# io-board-b-h.net
KiCad netlist of a schematic drawn in EAGLE
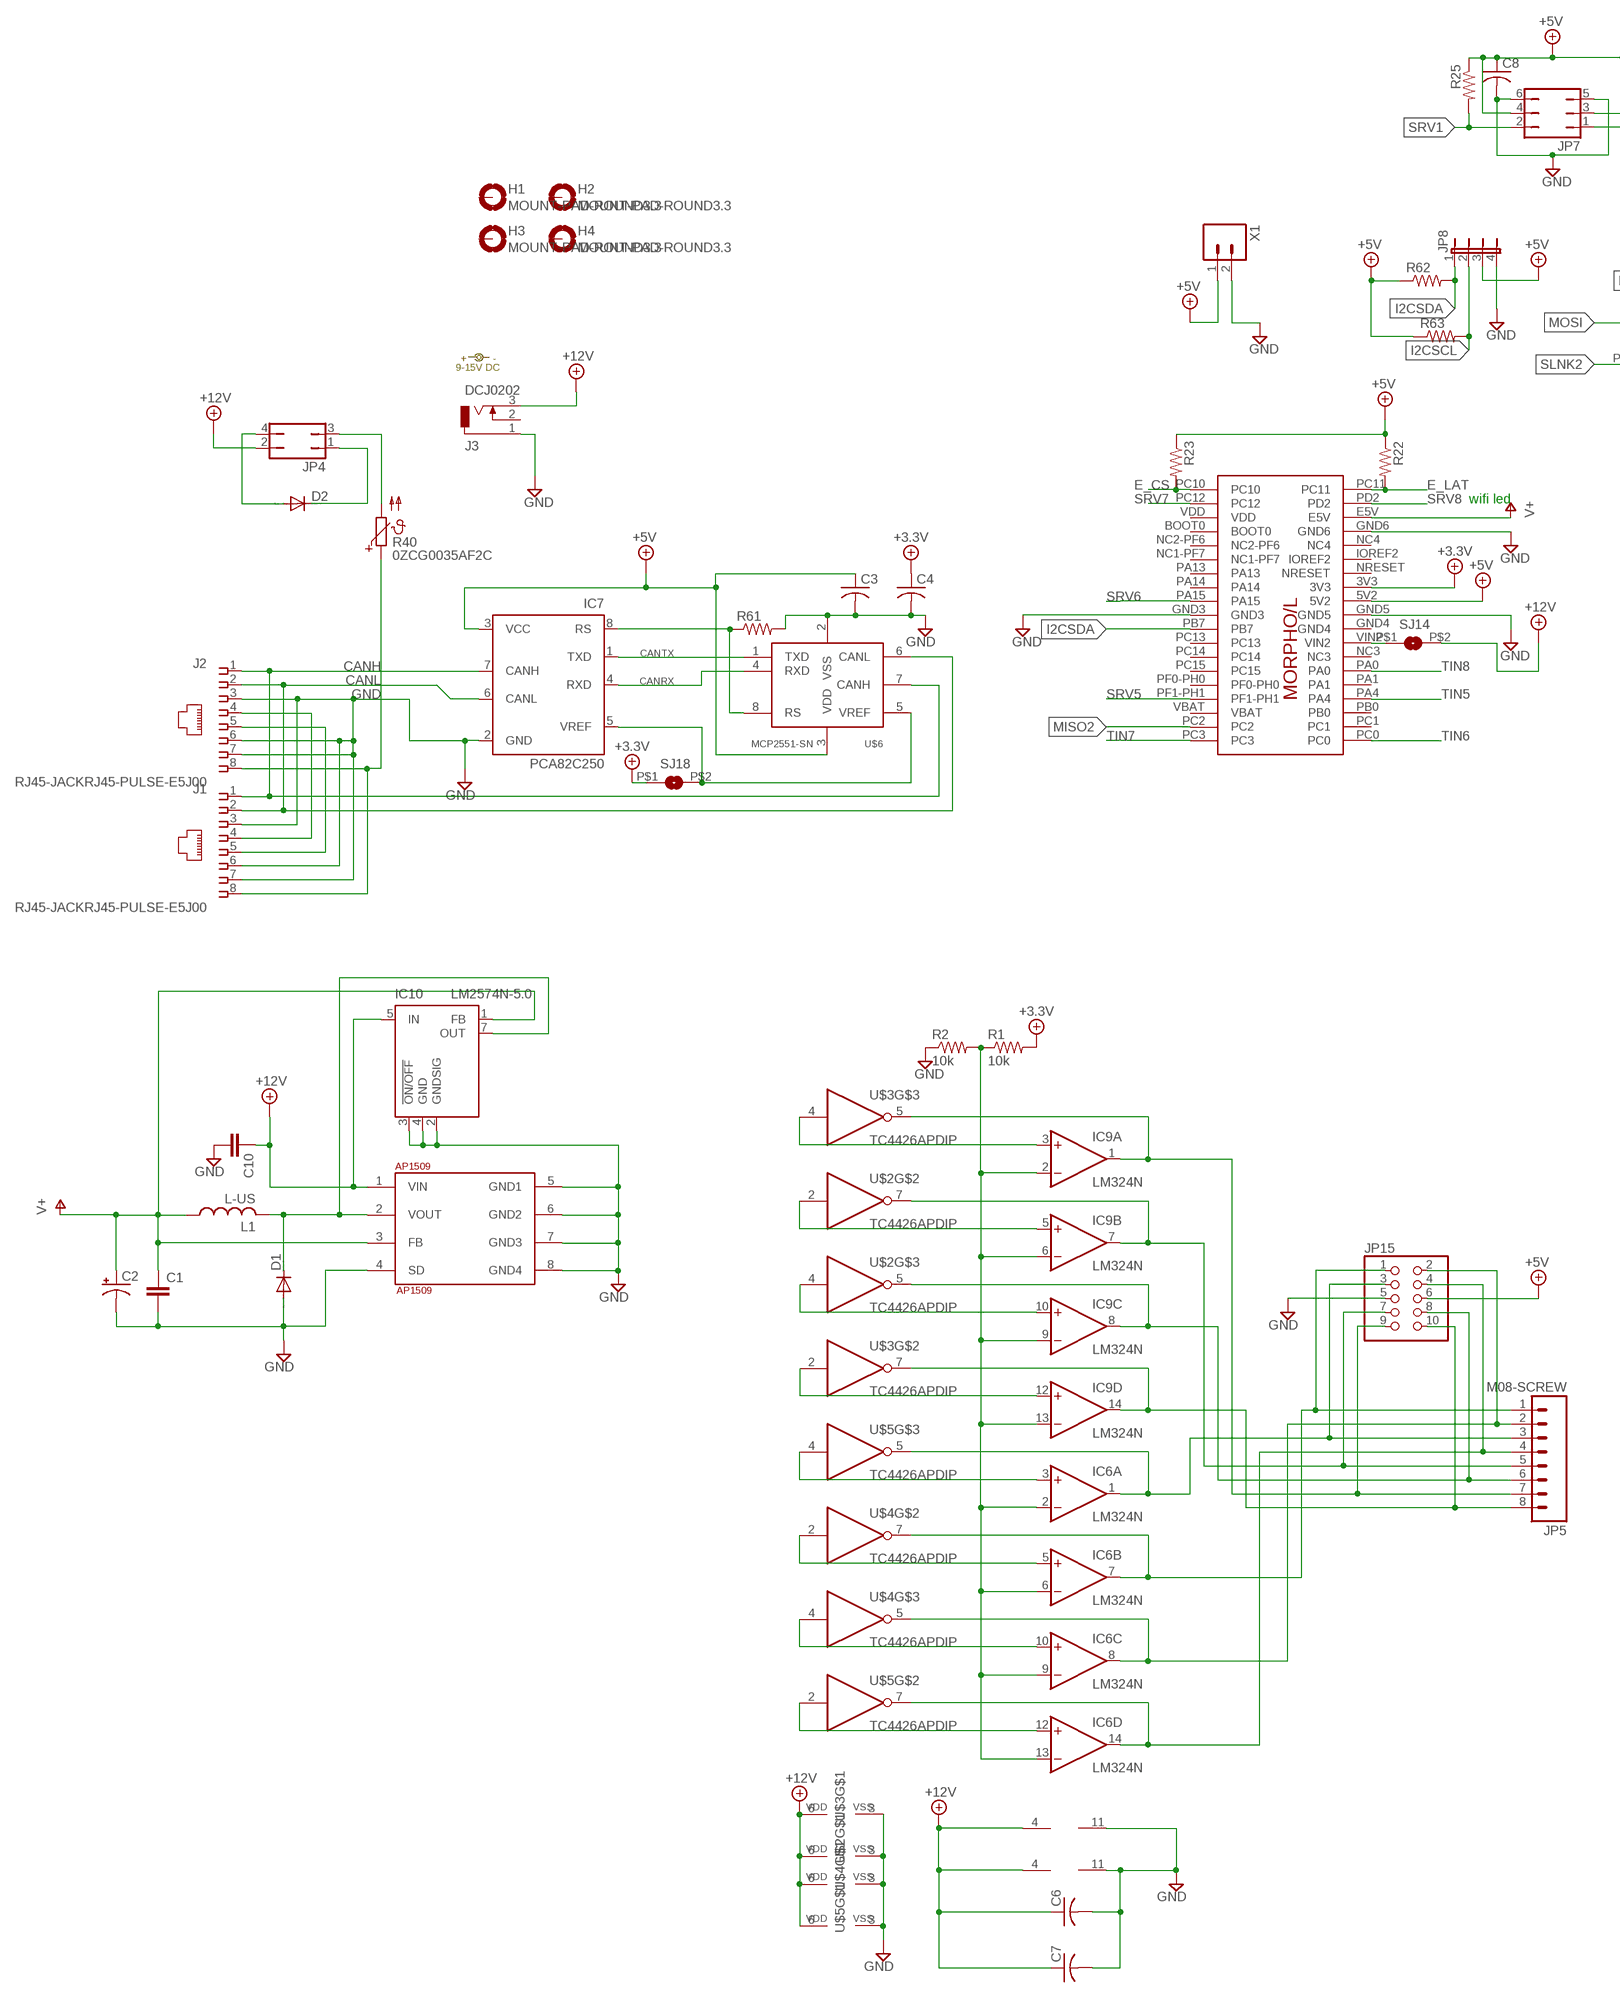
[diagram p0: schematic, sheet 1, part 1 of 2]
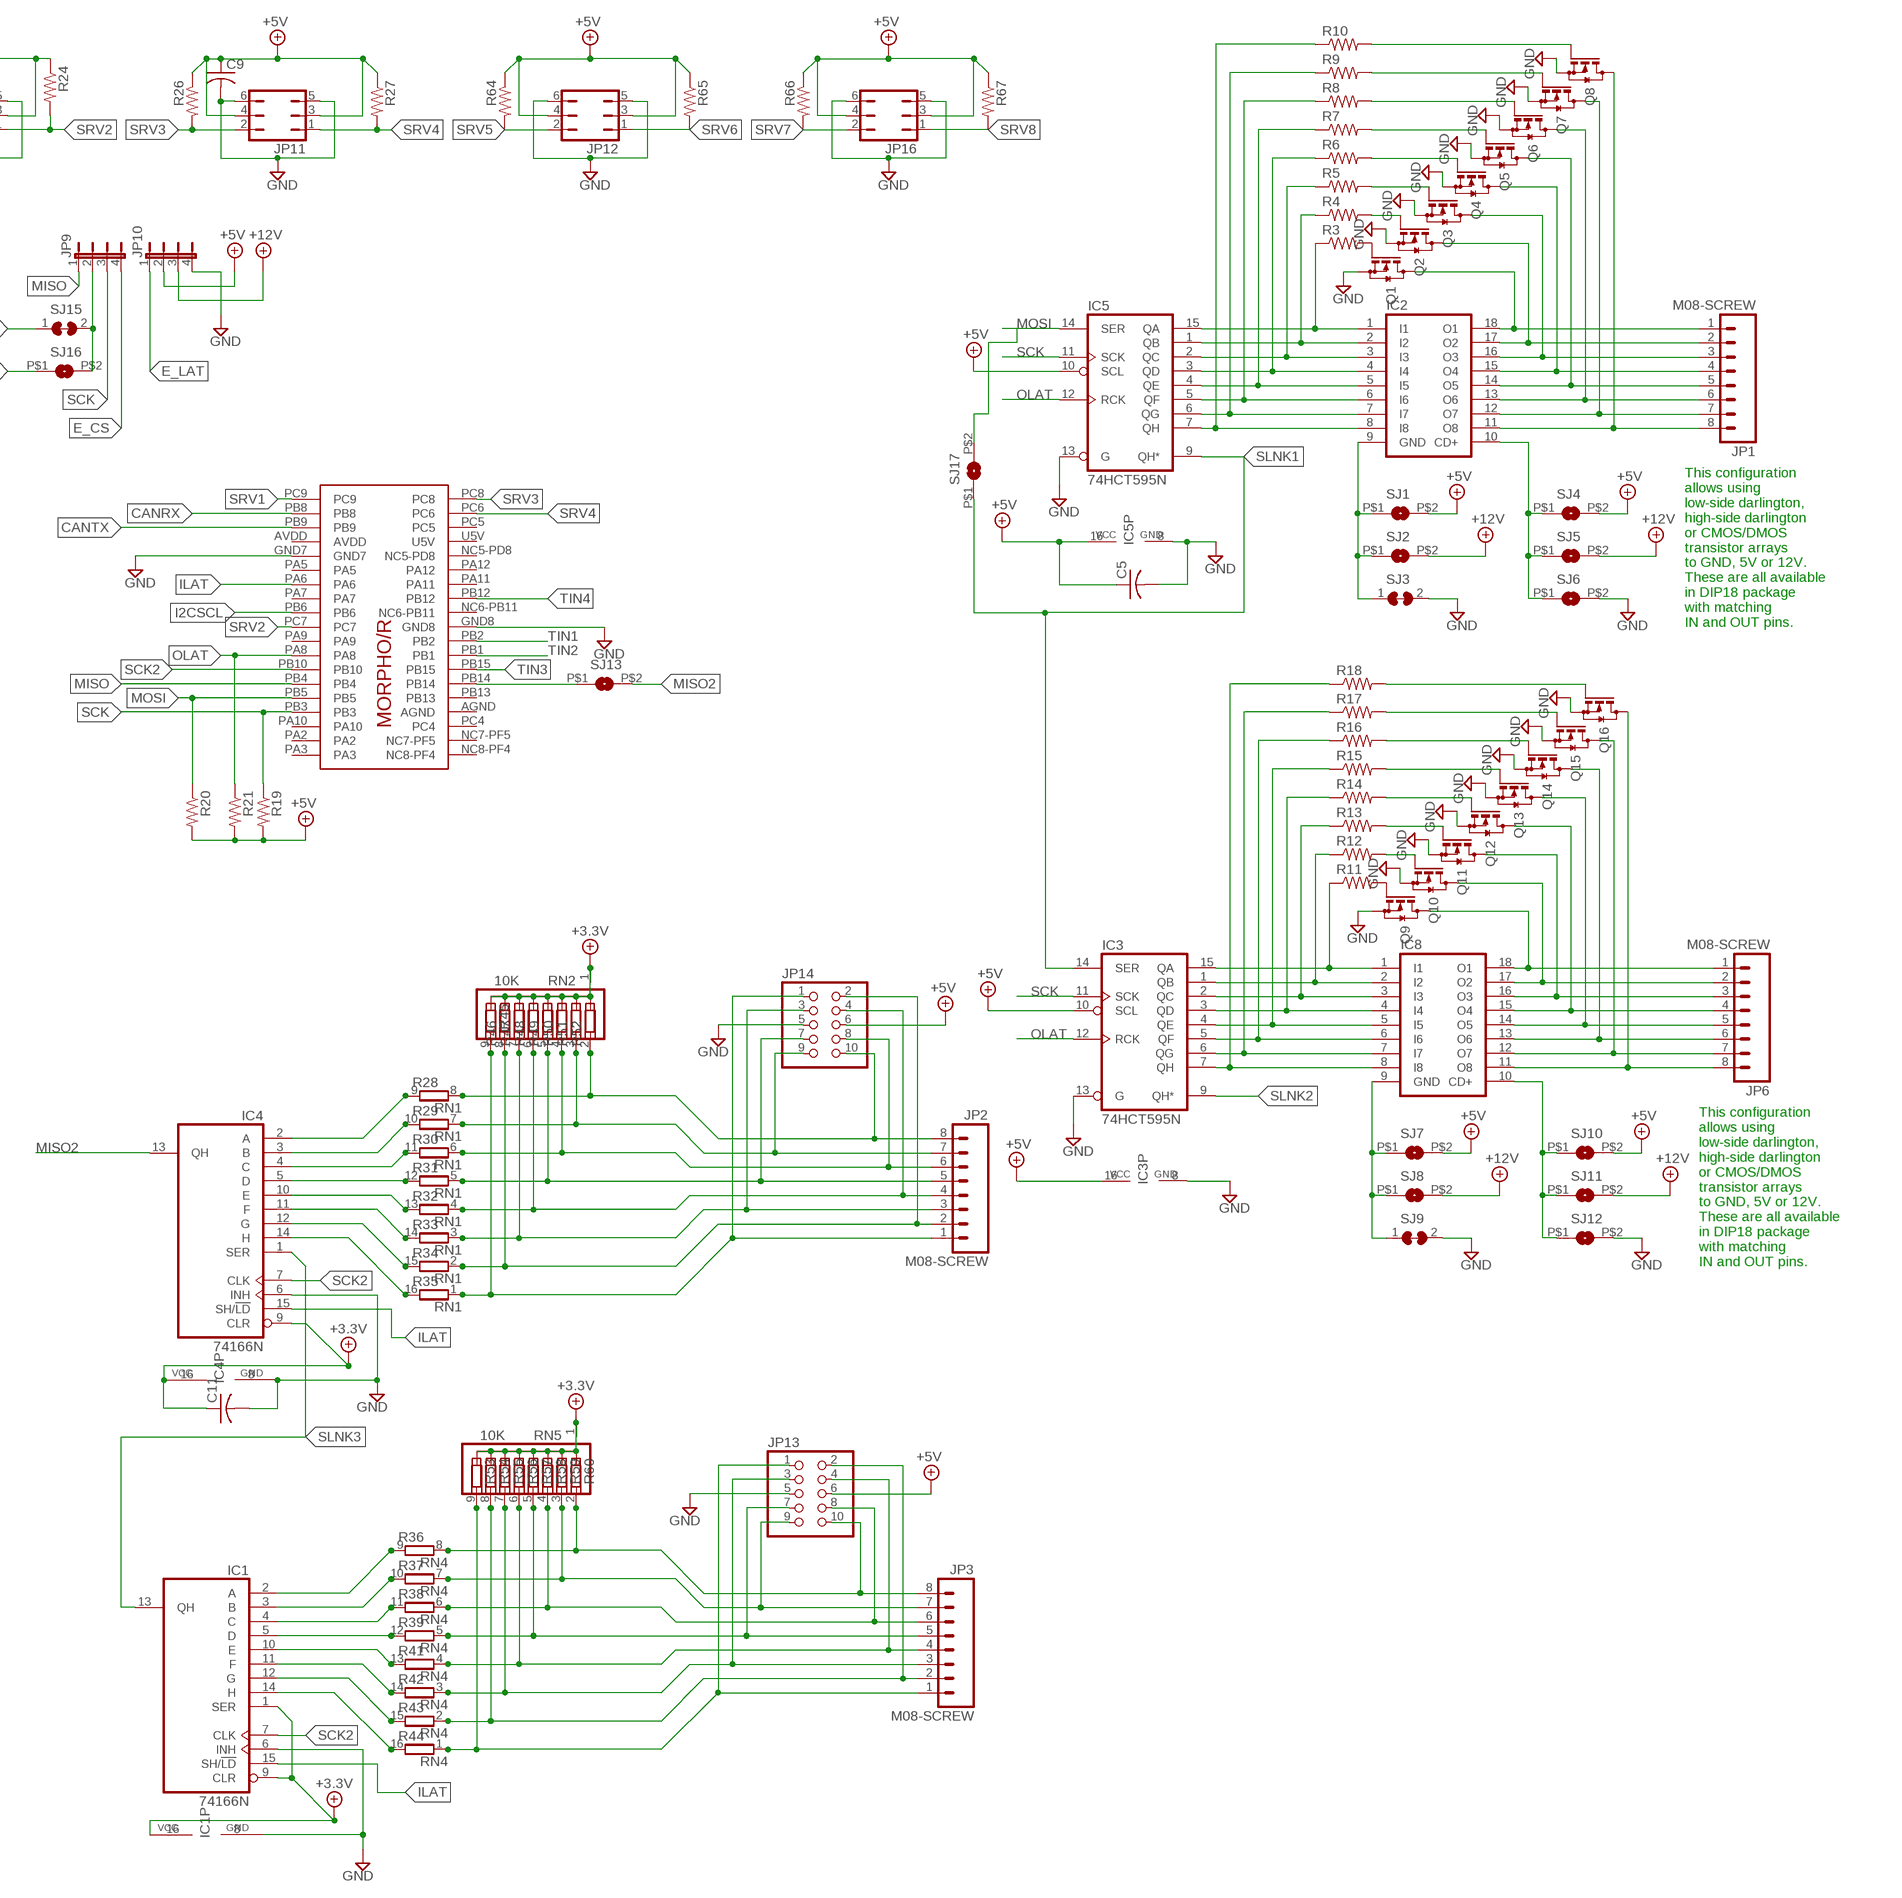
[diagram p1: schematic, sheet 1, part 2 of 2]

(export (version "E")
  (design (tool "Eeschema 10.0.6"))
  (components
    (comp (ref "+12V")
      (value "9-15V DC")
      (footprint "eagle-import:POWER_USAGE")
      (libsource (lib "eagle-import") (part "DOC-POWER_LABEL"))
    )
    (comp (ref "AP1509")
      (value "AP1509")
      (footprint "eagle-import:SO-08")
      (libsource (lib "eagle-import") (part "AP1509"))
    )
    (comp (ref "C1")
      (value "C-EUC1206")
      (footprint "eagle-import:C1206")
      (libsource (lib "eagle-import") (part "C-EUC1206"))
    )
    (comp (ref "C2")
      (value "CPOL-USE2.5-5")
      (footprint "eagle-import:E2,5-5")
      (libsource (lib "eagle-import") (part "CPOL-USE2.5-5"))
    )
    (comp (ref "C3")
      (value "C-USC0805")
      (footprint "eagle-import:C0805")
      (libsource (lib "eagle-import") (part "C-USC0805"))
    )
    (comp (ref "C4")
      (value "C-USC0805")
      (footprint "eagle-import:C0805")
      (libsource (lib "eagle-import") (part "C-USC0805"))
    )
    (comp (ref "C5")
      (value "C-USC0805")
      (footprint "eagle-import:C0805")
      (libsource (lib "eagle-import") (part "C-USC0805"))
    )
    (comp (ref "C6")
      (value "C-USC1206")
      (footprint "eagle-import:C1206")
      (libsource (lib "eagle-import") (part "C-USC1206"))
    )
    (comp (ref "C7")
      (value "C-USC1206")
      (footprint "eagle-import:C1206")
      (libsource (lib "eagle-import") (part "C-USC1206"))
    )
    (comp (ref "C8")
      (value "C-USC1206")
      (footprint "eagle-import:C1206")
      (libsource (lib "eagle-import") (part "C-USC1206"))
    )
    (comp (ref "C9")
      (value "C-USC1206")
      (footprint "eagle-import:C1206")
      (libsource (lib "eagle-import") (part "C-USC1206"))
    )
    (comp (ref "C10")
      (value "C-EUC1206")
      (footprint "eagle-import:C1206")
      (libsource (lib "eagle-import") (part "C-EUC1206"))
    )
    (comp (ref "C11")
      (value "C-USC0805")
      (footprint "eagle-import:C0805")
      (libsource (lib "eagle-import") (part "C-USC0805"))
    )
    (comp (ref "D1")
      (value "DIODE-DO41-7.6")
      (footprint "eagle-import:DO41-7.6")
      (libsource (lib "eagle-import") (part "DIODE-DO41-7.6"))
    )
    (comp (ref "D2")
      (value "DIODE-DO41-7.6")
      (footprint "eagle-import:DO41-7.6")
      (libsource (lib "eagle-import") (part "DIODE-DO41-7.6"))
    )
    (comp (ref "H1")
      (value "MOUNT-PAD-ROUND3.3")
      (footprint "eagle-import:3,3-PAD")
      (libsource (lib "eagle-import") (part "MOUNT-PAD-ROUND3.3"))
    )
    (comp (ref "H2")
      (value "MOUNT-PAD-ROUND3.3")
      (footprint "eagle-import:3,3-PAD")
      (libsource (lib "eagle-import") (part "MOUNT-PAD-ROUND3.3"))
    )
    (comp (ref "H3")
      (value "MOUNT-PAD-ROUND3.3")
      (footprint "eagle-import:3,3-PAD")
      (libsource (lib "eagle-import") (part "MOUNT-PAD-ROUND3.3"))
    )
    (comp (ref "H4")
      (value "MOUNT-PAD-ROUND3.3")
      (footprint "eagle-import:3,3-PAD")
      (libsource (lib "eagle-import") (part "MOUNT-PAD-ROUND3.3"))
    )
    (comp (ref "IC1")
      (value "74166N")
      (footprint "eagle-import:DIL16")
      (libsource (lib "eagle-import") (part "74166N"))
    )
    (comp (ref "IC2")
      (value "ULN2803A")
      (footprint "eagle-import:DIL18-THIN")
      (libsource (lib "eagle-import") (part "ULN2803A"))
    )
    (comp (ref "IC3")
      (value "74HCT595N")
      (footprint "eagle-import:DIL16")
      (libsource (lib "eagle-import") (part "74595NHCT"))
    )
    (comp (ref "IC4")
      (value "74166N")
      (footprint "eagle-import:DIL16")
      (libsource (lib "eagle-import") (part "74166N"))
    )
    (comp (ref "IC5")
      (value "74HCT595N")
      (footprint "eagle-import:DIL16")
      (libsource (lib "eagle-import") (part "74595NHCT"))
    )
    (comp (ref "IC6")
      (value "LM324N")
      (footprint "eagle-import:DIL14")
      (libsource (lib "eagle-import") (part "LM324N"))
    )
    (comp (ref "IC7")
      (value "PCA82C250")
      (footprint "eagle-import:DIL08")
      (libsource (lib "eagle-import") (part "PCA82C250"))
    )
    (comp (ref "IC8")
      (value "ULN2803A")
      (footprint "eagle-import:DIL18-THIN")
      (libsource (lib "eagle-import") (part "ULN2803A"))
    )
    (comp (ref "IC9")
      (value "LM324N")
      (footprint "eagle-import:DIL14")
      (libsource (lib "eagle-import") (part "LM324N"))
    )
    (comp (ref "IC10")
      (value "LM2574N-5.0")
      (footprint "eagle-import:DIL08")
      (libsource (lib "eagle-import") (part "LM2574?-N5.0"))
    )
    (comp (ref "J1")
      (value "RJ45-JACKRJ45-PULSE-E5J00")
      (footprint "eagle-import:RJ45-PULSE-E5J88")
      (libsource (lib "eagle-import") (part "RJ45-JACKRJ45-PULSE-E5J00"))
    )
    (comp (ref "J2")
      (value "RJ45-JACKRJ45-PULSE-E5J00")
      (footprint "eagle-import:RJ45-PULSE-E5J88")
      (libsource (lib "eagle-import") (part "RJ45-JACKRJ45-PULSE-E5J00"))
    )
    (comp (ref "J3")
      (value "DCJ0202")
      (footprint "eagle-import:DCJ0202")
      (libsource (lib "eagle-import") (part "DCJ0202"))
    )
    (comp (ref "JP1")
      (value "M08-SCREW")
      (footprint "eagle-import:1X08_TERMINAL")
      (libsource (lib "eagle-import") (part "M08-SCREW"))
    )
    (comp (ref "JP2")
      (value "M08-SCREW")
      (footprint "eagle-import:1X08_TERMINAL")
      (libsource (lib "eagle-import") (part "M08-SCREW"))
    )
    (comp (ref "JP3")
      (value "M08-SCREW")
      (footprint "eagle-import:1X08_TERMINAL")
      (libsource (lib "eagle-import") (part "M08-SCREW"))
    )
    (comp (ref "JP4")
      (value "JP2Q")
      (footprint "eagle-import:JP2Q")
      (libsource (lib "eagle-import") (part "JP2Q"))
    )
    (comp (ref "JP5")
      (value "M08-SCREW")
      (footprint "eagle-import:1X08_TERMINAL")
      (libsource (lib "eagle-import") (part "M08-SCREW"))
    )
    (comp (ref "JP6")
      (value "M08-SCREW")
      (footprint "eagle-import:1X08_TERMINAL")
      (libsource (lib "eagle-import") (part "M08-SCREW"))
    )
    (comp (ref "JP7")
      (value "JP3Q")
      (footprint "eagle-import:JP3Q")
      (libsource (lib "eagle-import") (part "JP3Q"))
    )
    (comp (ref "JP8")
      (value "JP4-FLAT")
      (footprint "eagle-import:JP4F")
      (libsource (lib "eagle-import") (part "JP4-FLAT"))
    )
    (comp (ref "JP9")
      (value "JP4-FLAT")
      (footprint "eagle-import:JP4F")
      (libsource (lib "eagle-import") (part "JP4-FLAT"))
    )
    (comp (ref "JP10")
      (value "JP4-FLAT")
      (footprint "eagle-import:JP4F")
      (libsource (lib "eagle-import") (part "JP4-FLAT"))
    )
    (comp (ref "JP11")
      (value "JP3Q")
      (footprint "eagle-import:JP3Q")
      (libsource (lib "eagle-import") (part "JP3Q"))
    )
    (comp (ref "JP12")
      (value "JP3Q")
      (footprint "eagle-import:JP3Q")
      (libsource (lib "eagle-import") (part "JP3Q"))
    )
    (comp (ref "JP13")
      (value "PINHD-2X5CN")
      (footprint "eagle-import:CON10M")
      (libsource (lib "eagle-import") (part "PINHD-2X5CN"))
    )
    (comp (ref "JP14")
      (value "PINHD-2X5CN")
      (footprint "eagle-import:CON10M")
      (libsource (lib "eagle-import") (part "PINHD-2X5CN"))
    )
    (comp (ref "JP15")
      (value "PINHD-2X5CN")
      (footprint "eagle-import:CON10M")
      (libsource (lib "eagle-import") (part "PINHD-2X5CN"))
    )
    (comp (ref "JP16")
      (value "JP3Q")
      (footprint "eagle-import:JP3Q")
      (libsource (lib "eagle-import") (part "JP3Q"))
    )
    (comp (ref "L1")
      (value "L-US")
      (footprint "eagle-import:L5-8,5")
      (libsource (lib "eagle-import") (part "L-US"))
    )
    (comp (ref "Q1")
      (value "BSS123")
      (footprint "eagle-import:SOT23")
      (libsource (lib "eagle-import") (part "BSS123"))
    )
    (comp (ref "Q2")
      (value "BSS123")
      (footprint "eagle-import:SOT23")
      (libsource (lib "eagle-import") (part "BSS123"))
    )
    (comp (ref "Q3")
      (value "BSS123")
      (footprint "eagle-import:SOT23")
      (libsource (lib "eagle-import") (part "BSS123"))
    )
    (comp (ref "Q4")
      (value "BSS123")
      (footprint "eagle-import:SOT23")
      (libsource (lib "eagle-import") (part "BSS123"))
    )
    (comp (ref "Q5")
      (value "BSS123")
      (footprint "eagle-import:SOT23")
      (libsource (lib "eagle-import") (part "BSS123"))
    )
    (comp (ref "Q6")
      (value "BSS123")
      (footprint "eagle-import:SOT23")
      (libsource (lib "eagle-import") (part "BSS123"))
    )
    (comp (ref "Q7")
      (value "BSS123")
      (footprint "eagle-import:SOT23")
      (libsource (lib "eagle-import") (part "BSS123"))
    )
    (comp (ref "Q8")
      (value "BSS123")
      (footprint "eagle-import:SOT23")
      (libsource (lib "eagle-import") (part "BSS123"))
    )
    (comp (ref "Q9")
      (value "BSS123")
      (footprint "eagle-import:SOT23")
      (libsource (lib "eagle-import") (part "BSS123"))
    )
    (comp (ref "Q10")
      (value "BSS123")
      (footprint "eagle-import:SOT23")
      (libsource (lib "eagle-import") (part "BSS123"))
    )
    (comp (ref "Q11")
      (value "BSS123")
      (footprint "eagle-import:SOT23")
      (libsource (lib "eagle-import") (part "BSS123"))
    )
    (comp (ref "Q12")
      (value "BSS123")
      (footprint "eagle-import:SOT23")
      (libsource (lib "eagle-import") (part "BSS123"))
    )
    (comp (ref "Q13")
      (value "BSS123")
      (footprint "eagle-import:SOT23")
      (libsource (lib "eagle-import") (part "BSS123"))
    )
    (comp (ref "Q14")
      (value "BSS123")
      (footprint "eagle-import:SOT23")
      (libsource (lib "eagle-import") (part "BSS123"))
    )
    (comp (ref "Q15")
      (value "BSS123")
      (footprint "eagle-import:SOT23")
      (libsource (lib "eagle-import") (part "BSS123"))
    )
    (comp (ref "Q16")
      (value "BSS123")
      (footprint "eagle-import:SOT23")
      (libsource (lib "eagle-import") (part "BSS123"))
    )
    (comp (ref "R1")
      (value "10k")
      (footprint "eagle-import:R0805")
      (libsource (lib "eagle-import") (part "R-US_R0805"))
    )
    (comp (ref "R2")
      (value "10k")
      (footprint "eagle-import:R0805")
      (libsource (lib "eagle-import") (part "R-US_R0805"))
    )
    (comp (ref "R3")
      (value "R-US_R0603")
      (footprint "eagle-import:R0603")
      (libsource (lib "eagle-import") (part "R-US_R0603"))
    )
    (comp (ref "R4")
      (value "R-US_R0603")
      (footprint "eagle-import:R0603")
      (libsource (lib "eagle-import") (part "R-US_R0603"))
    )
    (comp (ref "R5")
      (value "R-US_R0603")
      (footprint "eagle-import:R0603")
      (libsource (lib "eagle-import") (part "R-US_R0603"))
    )
    (comp (ref "R6")
      (value "R-US_R0603")
      (footprint "eagle-import:R0603")
      (libsource (lib "eagle-import") (part "R-US_R0603"))
    )
    (comp (ref "R7")
      (value "R-US_R0603")
      (footprint "eagle-import:R0603")
      (libsource (lib "eagle-import") (part "R-US_R0603"))
    )
    (comp (ref "R8")
      (value "R-US_R0603")
      (footprint "eagle-import:R0603")
      (libsource (lib "eagle-import") (part "R-US_R0603"))
    )
    (comp (ref "R9")
      (value "R-US_R0603")
      (footprint "eagle-import:R0603")
      (libsource (lib "eagle-import") (part "R-US_R0603"))
    )
    (comp (ref "R10")
      (value "R-US_R0603")
      (footprint "eagle-import:R0603")
      (libsource (lib "eagle-import") (part "R-US_R0603"))
    )
    (comp (ref "R11")
      (value "R-US_R0603")
      (footprint "eagle-import:R0603")
      (libsource (lib "eagle-import") (part "R-US_R0603"))
    )
    (comp (ref "R12")
      (value "R-US_R0603")
      (footprint "eagle-import:R0603")
      (libsource (lib "eagle-import") (part "R-US_R0603"))
    )
    (comp (ref "R13")
      (value "R-US_R0603")
      (footprint "eagle-import:R0603")
      (libsource (lib "eagle-import") (part "R-US_R0603"))
    )
    (comp (ref "R14")
      (value "R-US_R0603")
      (footprint "eagle-import:R0603")
      (libsource (lib "eagle-import") (part "R-US_R0603"))
    )
    (comp (ref "R15")
      (value "R-US_R0603")
      (footprint "eagle-import:R0603")
      (libsource (lib "eagle-import") (part "R-US_R0603"))
    )
    (comp (ref "R16")
      (value "R-US_R0603")
      (footprint "eagle-import:R0603")
      (libsource (lib "eagle-import") (part "R-US_R0603"))
    )
    (comp (ref "R17")
      (value "R-US_R0603")
      (footprint "eagle-import:R0603")
      (libsource (lib "eagle-import") (part "R-US_R0603"))
    )
    (comp (ref "R18")
      (value "R-US_R0603")
      (footprint "eagle-import:R0603")
      (libsource (lib "eagle-import") (part "R-US_R0603"))
    )
    (comp (ref "R19")
      (value "R-US_R0805")
      (footprint "eagle-import:R0805")
      (libsource (lib "eagle-import") (part "rcl_334_R-US_R0805"))
    )
    (comp (ref "R20")
      (value "R-US_R0805")
      (footprint "eagle-import:R0805")
      (libsource (lib "eagle-import") (part "rcl_334_R-US_R0805"))
    )
    (comp (ref "R21")
      (value "R-US_R0805")
      (footprint "eagle-import:R0805")
      (libsource (lib "eagle-import") (part "rcl_334_R-US_R0805"))
    )
    (comp (ref "R22")
      (value "R-US_R0805")
      (footprint "eagle-import:R0805")
      (libsource (lib "eagle-import") (part "rcl_334_R-US_R0805"))
    )
    (comp (ref "R23")
      (value "R-US_R0805")
      (footprint "eagle-import:R0805")
      (libsource (lib "eagle-import") (part "rcl_334_R-US_R0805"))
    )
    (comp (ref "R24")
      (value "R-US_R0805")
      (footprint "eagle-import:R0805")
      (libsource (lib "eagle-import") (part "rcl_334_R-US_R0805"))
    )
    (comp (ref "R25")
      (value "R-US_R0805")
      (footprint "eagle-import:R0805")
      (libsource (lib "eagle-import") (part "rcl_334_R-US_R0805"))
    )
    (comp (ref "R26")
      (value "R-US_R0805")
      (footprint "eagle-import:R0805")
      (libsource (lib "eagle-import") (part "rcl_334_R-US_R0805"))
    )
    (comp (ref "R27")
      (value "R-US_R0805")
      (footprint "eagle-import:R0805")
      (libsource (lib "eagle-import") (part "rcl_334_R-US_R0805"))
    )
    (comp (ref "R28")
      (value "R-EU_R0603")
      (footprint "eagle-import:R0603")
      (libsource (lib "eagle-import") (part "R-EU_R0603"))
    )
    (comp (ref "R29")
      (value "R-EU_R0603")
      (footprint "eagle-import:R0603")
      (libsource (lib "eagle-import") (part "R-EU_R0603"))
    )
    (comp (ref "R30")
      (value "R-EU_R0603")
      (footprint "eagle-import:R0603")
      (libsource (lib "eagle-import") (part "R-EU_R0603"))
    )
    (comp (ref "R31")
      (value "R-EU_R0603")
      (footprint "eagle-import:R0603")
      (libsource (lib "eagle-import") (part "R-EU_R0603"))
    )
    (comp (ref "R32")
      (value "R-EU_R0603")
      (footprint "eagle-import:R0603")
      (libsource (lib "eagle-import") (part "R-EU_R0603"))
    )
    (comp (ref "R33")
      (value "R-EU_R0603")
      (footprint "eagle-import:R0603")
      (libsource (lib "eagle-import") (part "R-EU_R0603"))
    )
    (comp (ref "R34")
      (value "R-EU_R0603")
      (footprint "eagle-import:R0603")
      (libsource (lib "eagle-import") (part "R-EU_R0603"))
    )
    (comp (ref "R35")
      (value "R-EU_R0603")
      (footprint "eagle-import:R0603")
      (libsource (lib "eagle-import") (part "R-EU_R0603"))
    )
    (comp (ref "R36")
      (value "R-EU_R0603")
      (footprint "eagle-import:R0603")
      (libsource (lib "eagle-import") (part "R-EU_R0603"))
    )
    (comp (ref "R37")
      (value "R-EU_R0603")
      (footprint "eagle-import:R0603")
      (libsource (lib "eagle-import") (part "R-EU_R0603"))
    )
    (comp (ref "R38")
      (value "R-EU_R0603")
      (footprint "eagle-import:R0603")
      (libsource (lib "eagle-import") (part "R-EU_R0603"))
    )
    (comp (ref "R39")
      (value "R-EU_R0603")
      (footprint "eagle-import:R0603")
      (libsource (lib "eagle-import") (part "R-EU_R0603"))
    )
    (comp (ref "R40")
      (value "0ZCG0035AF2C")
      (footprint "eagle-import:PTC1812")
      (libsource (lib "eagle-import") (part "PTC_1812"))
    )
    (comp (ref "R41")
      (value "R-EU_R0603")
      (footprint "eagle-import:R0603")
      (libsource (lib "eagle-import") (part "R-EU_R0603"))
    )
    (comp (ref "R42")
      (value "R-EU_R0603")
      (footprint "eagle-import:R0603")
      (libsource (lib "eagle-import") (part "R-EU_R0603"))
    )
    (comp (ref "R43")
      (value "R-EU_R0603")
      (footprint "eagle-import:R0603")
      (libsource (lib "eagle-import") (part "R-EU_R0603"))
    )
    (comp (ref "R44")
      (value "R-EU_R0603")
      (footprint "eagle-import:R0603")
      (libsource (lib "eagle-import") (part "R-EU_R0603"))
    )
    (comp (ref "R45")
      (value "R-EU_R0603")
      (footprint "eagle-import:R0603")
      (libsource (lib "eagle-import") (part "R-EU_R0603"))
    )
    (comp (ref "R46")
      (value "R-EU_R0603")
      (footprint "eagle-import:R0603")
      (libsource (lib "eagle-import") (part "R-EU_R0603"))
    )
    (comp (ref "R47")
      (value "R-EU_R0603")
      (footprint "eagle-import:R0603")
      (libsource (lib "eagle-import") (part "R-EU_R0603"))
    )
    (comp (ref "R48")
      (value "R-EU_R0603")
      (footprint "eagle-import:R0603")
      (libsource (lib "eagle-import") (part "R-EU_R0603"))
    )
    (comp (ref "R49")
      (value "R-EU_R0603")
      (footprint "eagle-import:R0603")
      (libsource (lib "eagle-import") (part "R-EU_R0603"))
    )
    (comp (ref "R50")
      (value "R-EU_R0603")
      (footprint "eagle-import:R0603")
      (libsource (lib "eagle-import") (part "R-EU_R0603"))
    )
    (comp (ref "R51")
      (value "R-EU_R0603")
      (footprint "eagle-import:R0603")
      (libsource (lib "eagle-import") (part "R-EU_R0603"))
    )
    (comp (ref "R52")
      (value "R-EU_R0603")
      (footprint "eagle-import:R0603")
      (libsource (lib "eagle-import") (part "R-EU_R0603"))
    )
    (comp (ref "R53")
      (value "R-EU_R0603")
      (footprint "eagle-import:R0603")
      (libsource (lib "eagle-import") (part "R-EU_R0603"))
    )
    (comp (ref "R54")
      (value "R-EU_R0603")
      (footprint "eagle-import:R0603")
      (libsource (lib "eagle-import") (part "R-EU_R0603"))
    )
    (comp (ref "R55")
      (value "R-EU_R0603")
      (footprint "eagle-import:R0603")
      (libsource (lib "eagle-import") (part "R-EU_R0603"))
    )
    (comp (ref "R56")
      (value "R-EU_R0603")
      (footprint "eagle-import:R0603")
      (libsource (lib "eagle-import") (part "R-EU_R0603"))
    )
    (comp (ref "R57")
      (value "R-EU_R0603")
      (footprint "eagle-import:R0603")
      (libsource (lib "eagle-import") (part "R-EU_R0603"))
    )
    (comp (ref "R58")
      (value "R-EU_R0603")
      (footprint "eagle-import:R0603")
      (libsource (lib "eagle-import") (part "R-EU_R0603"))
    )
    (comp (ref "R59")
      (value "R-EU_R0603")
      (footprint "eagle-import:R0603")
      (libsource (lib "eagle-import") (part "R-EU_R0603"))
    )
    (comp (ref "R60")
      (value "R-EU_R0603")
      (footprint "eagle-import:R0603")
      (libsource (lib "eagle-import") (part "R-EU_R0603"))
    )
    (comp (ref "R61")
      (value "R-US_R0805")
      (footprint "eagle-import:R0805")
      (libsource (lib "eagle-import") (part "rcl_334_R-US_R0805"))
    )
    (comp (ref "R62")
      (value "R-US_R0805")
      (footprint "eagle-import:R0805")
      (libsource (lib "eagle-import") (part "rcl_334_R-US_R0805"))
    )
    (comp (ref "R63")
      (value "R-US_R0805")
      (footprint "eagle-import:R0805")
      (libsource (lib "eagle-import") (part "rcl_334_R-US_R0805"))
    )
    (comp (ref "R64")
      (value "R-US_R0805")
      (footprint "eagle-import:R0805")
      (libsource (lib "eagle-import") (part "rcl_334_R-US_R0805"))
    )
    (comp (ref "R65")
      (value "R-US_R0805")
      (footprint "eagle-import:R0805")
      (libsource (lib "eagle-import") (part "rcl_334_R-US_R0805"))
    )
    (comp (ref "R66")
      (value "R-US_R0805")
      (footprint "eagle-import:R0805")
      (libsource (lib "eagle-import") (part "rcl_334_R-US_R0805"))
    )
    (comp (ref "R67")
      (value "R-US_R0805")
      (footprint "eagle-import:R0805")
      (libsource (lib "eagle-import") (part "rcl_334_R-US_R0805"))
    )
    (comp (ref "RN1")
      (value "8R-P")
      (footprint "eagle-import:DIL16")
      (libsource (lib "eagle-import") (part "8R-P"))
    )
    (comp (ref "RN2")
      (value "10K")
      (footprint "eagle-import:SIL9")
      (libsource (lib "eagle-import") (part "G08R"))
    )
    (comp (ref "RN4")
      (value "8R-P")
      (footprint "eagle-import:DIL16")
      (libsource (lib "eagle-import") (part "8R-P"))
    )
    (comp (ref "RN5")
      (value "10K")
      (footprint "eagle-import:SIL9")
      (libsource (lib "eagle-import") (part "G08R"))
    )
    (comp (ref "SJ1")
      (value "SJRND2")
      (footprint "eagle-import:SJ_RND2")
      (libsource (lib "eagle-import") (part "SJRND2"))
    )
    (comp (ref "SJ2")
      (value "SJRND2")
      (footprint "eagle-import:SJ_RND2")
      (libsource (lib "eagle-import") (part "SJRND2"))
    )
    (comp (ref "SJ3")
      (value "SJ-C")
      (footprint "eagle-import:SJW-C")
      (libsource (lib "eagle-import") (part "SJ-C"))
    )
    (comp (ref "SJ4")
      (value "SJRND2")
      (footprint "eagle-import:SJ_RND2")
      (libsource (lib "eagle-import") (part "SJRND2"))
    )
    (comp (ref "SJ5")
      (value "SJRND2")
      (footprint "eagle-import:SJ_RND2")
      (libsource (lib "eagle-import") (part "SJRND2"))
    )
    (comp (ref "SJ6")
      (value "SJRND2")
      (footprint "eagle-import:SJ_RND2")
      (libsource (lib "eagle-import") (part "SJRND2"))
    )
    (comp (ref "SJ7")
      (value "SJRND2")
      (footprint "eagle-import:SJ_RND2")
      (libsource (lib "eagle-import") (part "SJRND2"))
    )
    (comp (ref "SJ8")
      (value "SJRND2")
      (footprint "eagle-import:SJ_RND2")
      (libsource (lib "eagle-import") (part "SJRND2"))
    )
    (comp (ref "SJ9")
      (value "SJ-C")
      (footprint "eagle-import:SJW-C")
      (libsource (lib "eagle-import") (part "SJ-C"))
    )
    (comp (ref "SJ10")
      (value "SJRND2")
      (footprint "eagle-import:SJ_RND2")
      (libsource (lib "eagle-import") (part "SJRND2"))
    )
    (comp (ref "SJ11")
      (value "SJRND2")
      (footprint "eagle-import:SJ_RND2")
      (libsource (lib "eagle-import") (part "SJRND2"))
    )
    (comp (ref "SJ12")
      (value "SJRND2")
      (footprint "eagle-import:SJ_RND2")
      (libsource (lib "eagle-import") (part "SJRND2"))
    )
    (comp (ref "SJ13")
      (value "SJRND2")
      (footprint "eagle-import:SJ_RND2")
      (libsource (lib "eagle-import") (part "SJRND2"))
    )
    (comp (ref "SJ14")
      (value "SJRND2")
      (footprint "eagle-import:SJ_RND2")
      (libsource (lib "eagle-import") (part "SJRND2"))
    )
    (comp (ref "SJ15")
      (value "SJ-C")
      (footprint "eagle-import:SJW-C")
      (libsource (lib "eagle-import") (part "SJ-C"))
    )
    (comp (ref "SJ16")
      (value "SJRND2")
      (footprint "eagle-import:SJ_RND2")
      (libsource (lib "eagle-import") (part "SJRND2"))
    )
    (comp (ref "SJ17")
      (value "SJRND2")
      (footprint "eagle-import:SJ_RND2")
      (libsource (lib "eagle-import") (part "SJRND2"))
    )
    (comp (ref "SJ18")
      (value "SJRND2")
      (footprint "eagle-import:SJ_RND2")
      (libsource (lib "eagle-import") (part "SJRND2"))
    )
    (comp (ref "U$1")
      (value "NUCLEO_64_GENERIC")
      (footprint "eagle-import:NUCLEO_BRD_BASE64")
      (libsource (lib "eagle-import") (part "NUCLEO_64_GENERIC"))
    )
    (comp (ref "U$2")
      (value "TC4426APDIP")
      (footprint "eagle-import:DIL08-LONG")
      (libsource (lib "eagle-import") (part "TC4426APDIP"))
    )
    (comp (ref "U$3")
      (value "TC4426APDIP")
      (footprint "eagle-import:DIL08-LONG")
      (libsource (lib "eagle-import") (part "TC4426APDIP"))
    )
    (comp (ref "U$4")
      (value "TC4426APDIP")
      (footprint "eagle-import:DIL08-LONG")
      (libsource (lib "eagle-import") (part "TC4426APDIP"))
    )
    (comp (ref "U$5")
      (value "TC4426APDIP")
      (footprint "eagle-import:DIL08-LONG")
      (libsource (lib "eagle-import") (part "TC4426APDIP"))
    )
    (comp (ref "U$6")
      (value "MCP2551-SN")
      (footprint "eagle-import:SO-08")
      (libsource (lib "eagle-import") (part "MCP2551-SN"))
    )
    (comp (ref "X1")
      (value "CONNECTOR-M023.5MM-LOCK")
      (footprint "eagle-import:SCREWTERMINAL-3.5MM-2_LOCK")
      (libsource (lib "eagle-import") (part "CONNECTOR-M023.5MM-LOCK"))
    )
  )
  (nets
    (net (code "1") (name "+3.3V") (class "Default")
      (node (ref "C11") (pin "1") (pinfunction "1_1") (pintype "passive"))
      (node (ref "C4") (pin "1") (pinfunction "1_1") (pintype "passive"))
      (node (ref "IC1") (pin "1") (pinfunction "SER_1") (pintype "input"))
      (node (ref "IC1") (pin "16") (pinfunction "VCC_16") (pintype "power_in"))
      (node (ref "IC1") (pin "9") (pinfunction "CLR_9") (pintype "input"))
      (node (ref "IC4") (pin "16") (pinfunction "VCC_16") (pintype "power_in"))
      (node (ref "IC4") (pin "9") (pinfunction "CLR_9") (pintype "input"))
      (node (ref "R1") (pin "2") (pinfunction "2_2") (pintype "passive"))
      (node (ref "R45") (pin "1") (pinfunction "1_1") (pintype "passive"))
      (node (ref "R46") (pin "2") (pinfunction "2_2") (pintype "passive"))
      (node (ref "R47") (pin "2") (pinfunction "2_2") (pintype "passive"))
      (node (ref "R48") (pin "2") (pinfunction "2_2") (pintype "passive"))
      (node (ref "R49") (pin "2") (pinfunction "2_2") (pintype "passive"))
      (node (ref "R50") (pin "2") (pinfunction "2_2") (pintype "passive"))
      (node (ref "R51") (pin "2") (pinfunction "2_2") (pintype "passive"))
      (node (ref "R52") (pin "2") (pinfunction "2_2") (pintype "passive"))
      (node (ref "R53") (pin "1") (pinfunction "1_1") (pintype "passive"))
      (node (ref "R54") (pin "1") (pinfunction "1_1") (pintype "passive"))
      (node (ref "R55") (pin "1") (pinfunction "1_1") (pintype "passive"))
      (node (ref "R56") (pin "1") (pinfunction "1_1") (pintype "passive"))
      (node (ref "R57") (pin "1") (pinfunction "1_1") (pintype "passive"))
      (node (ref "R58") (pin "1") (pinfunction "1_1") (pintype "passive"))
      (node (ref "R59") (pin "1") (pinfunction "1_1") (pintype "passive"))
      (node (ref "R60") (pin "1") (pinfunction "1_1") (pintype "passive"))
      (node (ref "RN2") (pin "1") (pinfunction "1_1") (pintype "passive"))
      (node (ref "RN5") (pin "1") (pinfunction "1_1") (pintype "passive"))
      (node (ref "SJ18") (pin "P$1") (pinfunction "1_P$1") (pintype "passive"))
      (node (ref "U$1") (pin "3V3") (pinfunction "3V3_3V3") (pintype "power_in"))
    )
    (net (code "2") (name "+5V") (class "Default")
      (node (ref "C3") (pin "1") (pinfunction "1_1") (pintype "passive"))
      (node (ref "C5") (pin "1") (pinfunction "1_1") (pintype "passive"))
      (node (ref "C8") (pin "1") (pinfunction "1_1") (pintype "passive"))
      (node (ref "C9") (pin "1") (pinfunction "1_1") (pintype "passive"))
      (node (ref "IC3") (pin "10") (pinfunction "SCL_10") (pintype "input"))
      (node (ref "IC3") (pin "16") (pinfunction "VCC_16") (pintype "power_in"))
      (node (ref "IC5") (pin "10") (pinfunction "SCL_10") (pintype "input"))
      (node (ref "IC5") (pin "16") (pinfunction "VCC_16") (pintype "power_in"))
      (node (ref "IC7") (pin "3") (pinfunction "VCC_3") (pintype "power_in"))
      (node (ref "JP10") (pin "2") (pinfunction "2_2") (pintype "passive"))
      (node (ref "JP11") (pin "3") (pinfunction "3_3") (pintype "passive"))
      (node (ref "JP11") (pin "4") (pinfunction "4_4") (pintype "passive"))
      (node (ref "JP12") (pin "3") (pinfunction "3_3") (pintype "passive"))
      (node (ref "JP12") (pin "4") (pinfunction "4_4") (pintype "passive"))
      (node (ref "JP13") (pin "6") (pinfunction "6_6") (pintype "passive"))
      (node (ref "JP14") (pin "6") (pinfunction "6_6") (pintype "passive"))
      (node (ref "JP15") (pin "6") (pinfunction "6_6") (pintype "passive"))
      (node (ref "JP16") (pin "3") (pinfunction "3_3") (pintype "passive"))
      (node (ref "JP16") (pin "4") (pinfunction "4_4") (pintype "passive"))
      (node (ref "JP7") (pin "3") (pinfunction "3_3") (pintype "passive"))
      (node (ref "JP7") (pin "4") (pinfunction "4_4") (pintype "passive"))
      (node (ref "JP8") (pin "3") (pinfunction "3_3") (pintype "passive"))
      (node (ref "R19") (pin "2") (pinfunction "2_2") (pintype "passive"))
      (node (ref "R20") (pin "2") (pinfunction "2_2") (pintype "passive"))
      (node (ref "R21") (pin "2") (pinfunction "2_2") (pintype "passive"))
      (node (ref "R22") (pin "1") (pinfunction "1_1") (pintype "passive"))
      (node (ref "R23") (pin "1") (pinfunction "1_1") (pintype "passive"))
      (node (ref "R24") (pin "1") (pinfunction "1_1") (pintype "passive"))
      (node (ref "R25") (pin "1") (pinfunction "1_1") (pintype "passive"))
      (node (ref "R26") (pin "1") (pinfunction "1_1") (pintype "passive"))
      (node (ref "R27") (pin "1") (pinfunction "1_1") (pintype "passive"))
      (node (ref "R62") (pin "1") (pinfunction "1_1") (pintype "passive"))
      (node (ref "R63") (pin "1") (pinfunction "1_1") (pintype "passive"))
      (node (ref "R64") (pin "1") (pinfunction "1_1") (pintype "passive"))
      (node (ref "R65") (pin "1") (pinfunction "1_1") (pintype "passive"))
      (node (ref "R66") (pin "1") (pinfunction "1_1") (pintype "passive"))
      (node (ref "R67") (pin "1") (pinfunction "1_1") (pintype "passive"))
      (node (ref "SJ1") (pin "P$2") (pinfunction "2_P$2") (pintype "passive"))
      (node (ref "SJ10") (pin "P$2") (pinfunction "2_P$2") (pintype "passive"))
      (node (ref "SJ4") (pin "P$2") (pinfunction "2_P$2") (pintype "passive"))
      (node (ref "SJ7") (pin "P$2") (pinfunction "2_P$2") (pintype "passive"))
      (node (ref "U$1") (pin "5V2") (pinfunction "5V2_5V2") (pintype "power_in"))
      (node (ref "U$6") (pin "3") (pinfunction "VDD_3") (pintype "power_in"))
      (node (ref "X1") (pin "1") (pinfunction "1_1") (pintype "passive"))
    )
    (net (code "3") (name "+12V") (class "Default")
      (node (ref "AP1509") (pin "1") (pinfunction "VIN_1") (pintype "bidirectional"))
      (node (ref "C10") (pin "1") (pinfunction "1_1") (pintype "passive"))
      (node (ref "C6") (pin "1") (pinfunction "1_1") (pintype "passive"))
      (node (ref "C7") (pin "1") (pinfunction "1_1") (pintype "passive"))
      (node (ref "IC10") (pin "5") (pinfunction "IN_5") (pintype "input"))
      (node (ref "IC6") (pin "4") (pinfunction "V+_4") (pintype "power_in"))
      (node (ref "IC9") (pin "4") (pinfunction "V+_4") (pintype "power_in"))
      (node (ref "J3") (pin "3") (pinfunction "3_3") (pintype "passive"))
      (node (ref "JP10") (pin "3") (pinfunction "3_3") (pintype "passive"))
      (node (ref "JP4") (pin "2") (pinfunction "2_2") (pintype "passive"))
      (node (ref "SJ11") (pin "P$2") (pinfunction "2_P$2") (pintype "passive"))
      (node (ref "SJ14") (pin "P$2") (pinfunction "2_P$2") (pintype "passive"))
      (node (ref "SJ2") (pin "P$2") (pinfunction "2_P$2") (pintype "passive"))
      (node (ref "SJ5") (pin "P$2") (pinfunction "2_P$2") (pintype "passive"))
      (node (ref "SJ8") (pin "P$2") (pinfunction "2_P$2") (pintype "passive"))
      (node (ref "U$2") (pin "6") (pinfunction "VDD_6") (pintype "power_in"))
      (node (ref "U$3") (pin "6") (pinfunction "VDD_6") (pintype "power_in"))
      (node (ref "U$4") (pin "6") (pinfunction "VDD_6") (pintype "power_in"))
      (node (ref "U$5") (pin "6") (pinfunction "VDD_6") (pintype "power_in"))
    )
    (net (code "4") (name "/AGND") (class "Default")
      (node (ref "U$1") (pin "AGND") (pinfunction "AGND_AGND") (pintype "power_in"))
    )
    (net (code "5") (name "/AVDD") (class "Default")
      (node (ref "U$1") (pin "AVDD") (pinfunction "AVDD_AVDD") (pintype "power_in"))
    )
    (net (code "6") (name "/CANH") (class "Default")
      (node (ref "IC7") (pin "7") (pinfunction "CANH_7") (pintype "bidirectional"))
      (node (ref "J1") (pin "1") (pinfunction "1_1") (pintype "passive"))
      (node (ref "J2") (pin "1") (pinfunction "1_1") (pintype "passive"))
      (node (ref "U$6") (pin "7") (pinfunction "CANH_7") (pintype "bidirectional"))
    )
    (net (code "7") (name "/CANL") (class "Default")
      (node (ref "IC7") (pin "6") (pinfunction "CANL_6") (pintype "bidirectional"))
      (node (ref "J1") (pin "2") (pinfunction "2_2") (pintype "passive"))
      (node (ref "J2") (pin "2") (pinfunction "2_2") (pintype "passive"))
      (node (ref "U$6") (pin "6") (pinfunction "CANL_6") (pintype "bidirectional"))
    )
    (net (code "8") (name "/GND4") (class "Default")
      (node (ref "U$1") (pin "GND4") (pinfunction "GND4_GND4") (pintype "power_in"))
    )
    (net (code "9") (name "/TIN1") (class "Default")
      (node (ref "IC9") (pin "3") (pinfunction "+IN_3") (pintype "input"))
      (node (ref "U$1") (pin "PB2") (pinfunction "PB2_PB2") (pintype "bidirectional"))
      (node (ref "U$3") (pin "4") (pinfunction "I_4") (pintype "input"))
    )
    (net (code "10") (name "/TIN2") (class "Default")
      (node (ref "IC9") (pin "5") (pinfunction "+IN_5") (pintype "input"))
      (node (ref "U$1") (pin "PB1") (pinfunction "PB1_PB1") (pintype "bidirectional"))
      (node (ref "U$2") (pin "2") (pinfunction "I_2") (pintype "input"))
    )
    (net (code "11") (name "/TIN5") (class "Default")
      (node (ref "IC6") (pin "3") (pinfunction "+IN_3") (pintype "input"))
      (node (ref "U$1") (pin "PA4") (pinfunction "PA4_PA4") (pintype "bidirectional"))
      (node (ref "U$5") (pin "4") (pinfunction "I_4") (pintype "input"))
    )
    (net (code "12") (name "/TIN6") (class "Default")
      (node (ref "IC6") (pin "5") (pinfunction "+IN_5") (pintype "input"))
      (node (ref "U$1") (pin "PC0") (pinfunction "PC0_PC0") (pintype "bidirectional"))
      (node (ref "U$4") (pin "2") (pinfunction "I_2") (pintype "input"))
    )
    (net (code "13") (name "/TIN7") (class "Default")
      (node (ref "IC6") (pin "10") (pinfunction "+IN_10") (pintype "input"))
      (node (ref "U$1") (pin "PC3") (pinfunction "PC3_PC3") (pintype "bidirectional"))
      (node (ref "U$4") (pin "4") (pinfunction "I_4") (pintype "input"))
    )
    (net (code "14") (name "/TIN8") (class "Default")
      (node (ref "IC6") (pin "12") (pinfunction "+IN_12") (pintype "input"))
      (node (ref "U$1") (pin "PA0") (pinfunction "PA0_PA0") (pintype "bidirectional"))
      (node (ref "U$5") (pin "2") (pinfunction "I_2") (pintype "input"))
    )
    (net (code "15") (name "/U5V") (class "Default")
      (node (ref "U$1") (pin "U5V") (pinfunction "U5V_U5V") (pintype "power_in"))
    )
    (net (code "16") (name "/VBAT") (class "Default")
      (node (ref "U$1") (pin "VBAT") (pinfunction "VBAT_VBAT") (pintype "power_in"))
    )
    (net (code "17") (name "/VDD") (class "Default")
      (node (ref "U$1") (pin "VDD") (pinfunction "VDD_VDD") (pintype "power_in"))
    )
    (net (code "18") (name "CANRX") (class "Default")
      (node (ref "IC7") (pin "4") (pinfunction "RXD_4") (pintype "output"))
      (node (ref "U$1") (pin "PB8") (pinfunction "PB8_PB8") (pintype "bidirectional"))
      (node (ref "U$6") (pin "4") (pinfunction "RXD_4") (pintype "bidirectional"))
    )
    (net (code "19") (name "CANTX") (class "Default")
      (node (ref "IC7") (pin "1") (pinfunction "TXD_1") (pintype "input"))
      (node (ref "U$1") (pin "PB9") (pinfunction "PB9_PB9") (pintype "bidirectional"))
      (node (ref "U$6") (pin "1") (pinfunction "TXD_1") (pintype "bidirectional"))
    )
    (net (code "20") (name "E_CS") (class "Default")
      (node (ref "JP9") (pin "4") (pinfunction "4_4") (pintype "passive"))
      (node (ref "R23") (pin "2") (pinfunction "2_2") (pintype "passive"))
      (node (ref "U$1") (pin "PC10") (pinfunction "PC10_PC10") (pintype "bidirectional"))
    )
    (net (code "21") (name "E_LAT") (class "Default")
      (node (ref "JP10") (pin "1") (pinfunction "1_1") (pintype "passive"))
      (node (ref "R22") (pin "2") (pinfunction "2_2") (pintype "passive"))
      (node (ref "U$1") (pin "PC11") (pinfunction "PC11_PC11") (pintype "bidirectional"))
    )
    (net (code "22") (name "GND") (class "Default")
      (node (ref "AP1509") (pin "4") (pinfunction "SD_4") (pintype "bidirectional"))
      (node (ref "AP1509") (pin "5") (pinfunction "GND1_5") (pintype "power_in"))
      (node (ref "AP1509") (pin "6") (pinfunction "GND2_6") (pintype "power_in"))
      (node (ref "AP1509") (pin "7") (pinfunction "GND3_7") (pintype "power_in"))
      (node (ref "AP1509") (pin "8") (pinfunction "GND4_8") (pintype "power_in"))
      (node (ref "C1") (pin "2") (pinfunction "2_2") (pintype "passive"))
      (node (ref "C10") (pin "2") (pinfunction "2_2") (pintype "passive"))
      (node (ref "C11") (pin "2") (pinfunction "2_2") (pintype "passive"))
      (node (ref "C2") (pin "-") (pinfunction "-_-") (pintype "passive"))
      (node (ref "C3") (pin "2") (pinfunction "2_2") (pintype "passive"))
      (node (ref "C4") (pin "2") (pinfunction "2_2") (pintype "passive"))
      (node (ref "C5") (pin "2") (pinfunction "2_2") (pintype "passive"))
      (node (ref "C6") (pin "2") (pinfunction "2_2") (pintype "passive"))
      (node (ref "C7") (pin "2") (pinfunction "2_2") (pintype "passive"))
      (node (ref "C8") (pin "2") (pinfunction "2_2") (pintype "passive"))
      (node (ref "C9") (pin "2") (pinfunction "2_2") (pintype "passive"))
      (node (ref "D1") (pin "A") (pinfunction "A_A") (pintype "passive"))
      (node (ref "IC1") (pin "6") (pinfunction "INH_6") (pintype "input"))
      (node (ref "IC1") (pin "8") (pinfunction "GND_8") (pintype "power_in"))
      (node (ref "IC10") (pin "2") (pinfunction "GNDSIG_2") (pintype "input"))
      (node (ref "IC10") (pin "3") (pinfunction "~{ON/OFF}_3") (pintype "input"))
      (node (ref "IC10") (pin "4") (pinfunction "GND_4") (pintype "power_in"))
      (node (ref "IC3") (pin "13") (pinfunction "G_13") (pintype "input"))
      (node (ref "IC3") (pin "8") (pinfunction "GND_8") (pintype "power_in"))
      (node (ref "IC4") (pin "6") (pinfunction "INH_6") (pintype "input"))
      (node (ref "IC4") (pin "8") (pinfunction "GND_8") (pintype "power_in"))
      (node (ref "IC5") (pin "13") (pinfunction "G_13") (pintype "input"))
      (node (ref "IC5") (pin "8") (pinfunction "GND_8") (pintype "power_in"))
      (node (ref "IC6") (pin "11") (pinfunction "V-_11") (pintype "power_in"))
      (node (ref "IC7") (pin "2") (pinfunction "GND_2") (pintype "power_in"))
      (node (ref "IC9") (pin "11") (pinfunction "V-_11") (pintype "power_in"))
      (node (ref "J1") (pin "3") (pinfunction "3_3") (pintype "passive"))
      (node (ref "J1") (pin "6") (pinfunction "6_6") (pintype "passive"))
      (node (ref "J1") (pin "7") (pinfunction "7_7") (pintype "passive"))
      (node (ref "J2") (pin "3") (pinfunction "3_3") (pintype "passive"))
      (node (ref "J2") (pin "6") (pinfunction "6_6") (pintype "passive"))
      (node (ref "J2") (pin "7") (pinfunction "7_7") (pintype "passive"))
      (node (ref "J3") (pin "1") (pinfunction "1_1") (pintype "passive"))
      (node (ref "JP10") (pin "4") (pinfunction "4_4") (pintype "passive"))
      (node (ref "JP11") (pin "5") (pinfunction "5_5") (pintype "passive"))
      (node (ref "JP11") (pin "6") (pinfunction "6_6") (pintype "passive"))
      (node (ref "JP12") (pin "5") (pinfunction "5_5") (pintype "passive"))
      (node (ref "JP12") (pin "6") (pinfunction "6_6") (pintype "passive"))
      (node (ref "JP13") (pin "5") (pinfunction "5_5") (pintype "passive"))
      (node (ref "JP14") (pin "5") (pinfunction "5_5") (pintype "passive"))
      (node (ref "JP15") (pin "5") (pinfunction "5_5") (pintype "passive"))
      (node (ref "JP16") (pin "5") (pinfunction "5_5") (pintype "passive"))
      (node (ref "JP16") (pin "6") (pinfunction "6_6") (pintype "passive"))
      (node (ref "JP7") (pin "5") (pinfunction "5_5") (pintype "passive"))
      (node (ref "JP7") (pin "6") (pinfunction "6_6") (pintype "passive"))
      (node (ref "JP8") (pin "4") (pinfunction "4_4") (pintype "passive"))
      (node (ref "Q1") (pin "2") (pinfunction "S_2") (pintype "passive"))
      (node (ref "Q10") (pin "2") (pinfunction "S_2") (pintype "passive"))
      (node (ref "Q11") (pin "2") (pinfunction "S_2") (pintype "passive"))
      (node (ref "Q12") (pin "2") (pinfunction "S_2") (pintype "passive"))
      (node (ref "Q13") (pin "2") (pinfunction "S_2") (pintype "passive"))
      (node (ref "Q14") (pin "2") (pinfunction "S_2") (pintype "passive"))
      (node (ref "Q15") (pin "2") (pinfunction "S_2") (pintype "passive"))
      (node (ref "Q16") (pin "2") (pinfunction "S_2") (pintype "passive"))
      (node (ref "Q2") (pin "2") (pinfunction "S_2") (pintype "passive"))
      (node (ref "Q3") (pin "2") (pinfunction "S_2") (pintype "passive"))
      (node (ref "Q4") (pin "2") (pinfunction "S_2") (pintype "passive"))
      (node (ref "Q5") (pin "2") (pinfunction "S_2") (pintype "passive"))
      (node (ref "Q6") (pin "2") (pinfunction "S_2") (pintype "passive"))
      (node (ref "Q7") (pin "2") (pinfunction "S_2") (pintype "passive"))
      (node (ref "Q8") (pin "2") (pinfunction "S_2") (pintype "passive"))
      (node (ref "Q9") (pin "2") (pinfunction "S_2") (pintype "passive"))
      (node (ref "R2") (pin "1") (pinfunction "1_1") (pintype "passive"))
      (node (ref "R61") (pin "2") (pinfunction "2_2") (pintype "passive"))
      (node (ref "SJ12") (pin "P$2") (pinfunction "2_P$2") (pintype "passive"))
      (node (ref "SJ3") (pin "2") (pinfunction "2_2") (pintype "passive"))
      (node (ref "SJ6") (pin "P$2") (pinfunction "2_P$2") (pintype "passive"))
      (node (ref "SJ9") (pin "2") (pinfunction "2_2") (pintype "passive"))
      (node (ref "U$1") (pin "GND3") (pinfunction "GND3_GND3") (pintype "power_in"))
      (node (ref "U$1") (pin "GND5") (pinfunction "GND5_GND5") (pintype "power_in"))
      (node (ref "U$1") (pin "GND6") (pinfunction "GND6_GND6") (pintype "power_in"))
      (node (ref "U$1") (pin "GND7") (pinfunction "GND7_GND7") (pintype "power_in"))
      (node (ref "U$1") (pin "GND8") (pinfunction "GND8_GND8") (pintype "power_in"))
      (node (ref "U$2") (pin "3") (pinfunction "VSS_3") (pintype "power_in"))
      (node (ref "U$3") (pin "3") (pinfunction "VSS_3") (pintype "power_in"))
      (node (ref "U$4") (pin "3") (pinfunction "VSS_3") (pintype "power_in"))
      (node (ref "U$5") (pin "3") (pinfunction "VSS_3") (pintype "power_in"))
      (node (ref "U$6") (pin "2") (pinfunction "VSS_2") (pintype "power_in"))
      (node (ref "X1") (pin "2") (pinfunction "2_2") (pintype "passive"))
    )
    (net (code "23") (name "I2CSCL") (class "Default")
      (node (ref "JP8") (pin "2") (pinfunction "2_2") (pintype "passive"))
      (node (ref "R63") (pin "2") (pinfunction "2_2") (pintype "passive"))
      (node (ref "U$1") (pin "PB6") (pinfunction "PB6_PB6") (pintype "bidirectional"))
    )
    (net (code "24") (name "I2CSDA") (class "Default")
      (node (ref "JP8") (pin "1") (pinfunction "1_1") (pintype "passive"))
      (node (ref "R62") (pin "2") (pinfunction "2_2") (pintype "passive"))
      (node (ref "U$1") (pin "PB7") (pinfunction "PB7_PB7") (pintype "bidirectional"))
    )
    (net (code "25") (name "ILAT") (class "Default")
      (node (ref "IC1") (pin "15") (pinfunction "SH/~{LD}_15") (pintype "input"))
      (node (ref "IC4") (pin "15") (pinfunction "SH/~{LD}_15") (pintype "input"))
      (node (ref "U$1") (pin "PA6") (pinfunction "PA6_PA6") (pintype "bidirectional"))
    )
    (net (code "26") (name "MISO") (class "Default")
      (node (ref "JP9") (pin "1") (pinfunction "1_1") (pintype "passive"))
      (node (ref "U$1") (pin "PB4") (pinfunction "PB4_PB4") (pintype "bidirectional"))
    )
    (net (code "27") (name "MISO2") (class "Default")
      (node (ref "IC4") (pin "13") (pinfunction "QH_13") (pintype "output"))
      (node (ref "SJ13") (pin "P$2") (pinfunction "2_P$2") (pintype "passive"))
      (node (ref "U$1") (pin "PC2") (pinfunction "PC2_PC2") (pintype "bidirectional"))
    )
    (net (code "28") (name "MOSI") (class "Default")
      (node (ref "IC5") (pin "14") (pinfunction "SER_14") (pintype "input"))
      (node (ref "R20") (pin "1") (pinfunction "1_1") (pintype "passive"))
      (node (ref "SJ15") (pin "1") (pinfunction "1_1") (pintype "passive"))
      (node (ref "SJ17") (pin "P$2") (pinfunction "2_P$2") (pintype "passive"))
      (node (ref "U$1") (pin "PB5") (pinfunction "PB5_PB5") (pintype "bidirectional"))
    )
    (net (code "29") (name "Net-(AP1509-VOUT)") (class "Default")
      (node (ref "AP1509") (pin "2") (pinfunction "VOUT_2") (pintype "bidirectional"))
      (node (ref "D1") (pin "C") (pinfunction "C_C") (pintype "passive"))
      (node (ref "IC10") (pin "7") (pinfunction "OUT_7") (pintype "passive"))
      (node (ref "L1") (pin "2") (pinfunction "2_2") (pintype "passive"))
    )
    (net (code "30") (name "Net-(D2-PadA)") (class "Default")
      (node (ref "D2") (pin "A") (pinfunction "A_A") (pintype "passive"))
      (node (ref "JP4") (pin "4") (pinfunction "4_4") (pintype "passive"))
    )
    (net (code "31") (name "Net-(D2-PadC)") (class "Default")
      (node (ref "D2") (pin "C") (pinfunction "C_C") (pintype "passive"))
      (node (ref "JP4") (pin "1") (pinfunction "1_1") (pintype "passive"))
    )
    (net (code "32") (name "Net-(IC1A-A)") (class "Default")
      (node (ref "IC1") (pin "2") (pinfunction "A_2") (pintype "input"))
      (node (ref "R36") (pin "1") (pinfunction "1_1") (pintype "passive"))
      (node (ref "RN4") (pin "9") (pinfunction "2_9") (pintype "passive"))
    )
    (net (code "33") (name "Net-(IC1A-B)") (class "Default")
      (node (ref "IC1") (pin "3") (pinfunction "B_3") (pintype "input"))
      (node (ref "R37") (pin "1") (pinfunction "1_1") (pintype "passive"))
      (node (ref "RN4") (pin "10") (pinfunction "2_10") (pintype "passive"))
    )
    (net (code "34") (name "Net-(IC1A-C)") (class "Default")
      (node (ref "IC1") (pin "4") (pinfunction "C_4") (pintype "input"))
      (node (ref "R38") (pin "1") (pinfunction "1_1") (pintype "passive"))
      (node (ref "RN4") (pin "11") (pinfunction "2_11") (pintype "passive"))
    )
    (net (code "35") (name "Net-(IC1A-D)") (class "Default")
      (node (ref "IC1") (pin "5") (pinfunction "D_5") (pintype "input"))
      (node (ref "R39") (pin "1") (pinfunction "1_1") (pintype "passive"))
      (node (ref "RN4") (pin "12") (pinfunction "2_12") (pintype "passive"))
    )
    (net (code "36") (name "Net-(IC1A-E)") (class "Default")
      (node (ref "IC1") (pin "10") (pinfunction "E_10") (pintype "input"))
      (node (ref "R41") (pin "1") (pinfunction "1_1") (pintype "passive"))
      (node (ref "RN4") (pin "13") (pinfunction "2_13") (pintype "passive"))
    )
    (net (code "37") (name "Net-(IC1A-F)") (class "Default")
      (node (ref "IC1") (pin "11") (pinfunction "F_11") (pintype "input"))
      (node (ref "R42") (pin "1") (pinfunction "1_1") (pintype "passive"))
      (node (ref "RN4") (pin "14") (pinfunction "2_14") (pintype "passive"))
    )
    (net (code "38") (name "Net-(IC1A-G)") (class "Default")
      (node (ref "IC1") (pin "12") (pinfunction "G_12") (pintype "input"))
      (node (ref "R43") (pin "1") (pinfunction "1_1") (pintype "passive"))
      (node (ref "RN4") (pin "15") (pinfunction "2_15") (pintype "passive"))
    )
    (net (code "39") (name "Net-(IC1A-H)") (class "Default")
      (node (ref "IC1") (pin "14") (pinfunction "H_14") (pintype "input"))
      (node (ref "R44") (pin "1") (pinfunction "1_1") (pintype "passive"))
      (node (ref "RN4") (pin "16") (pinfunction "2_16") (pintype "passive"))
    )
    (net (code "40") (name "Net-(IC2-CD+)") (class "Default")
      (node (ref "IC2") (pin "10") (pinfunction "CD+_10") (pintype "passive"))
      (node (ref "SJ4") (pin "P$1") (pinfunction "1_P$1") (pintype "passive"))
      (node (ref "SJ5") (pin "P$1") (pinfunction "1_P$1") (pintype "passive"))
      (node (ref "SJ6") (pin "P$1") (pinfunction "1_P$1") (pintype "passive"))
    )
    (net (code "41") (name "Net-(IC2-GND)") (class "Default")
      (node (ref "IC2") (pin "9") (pinfunction "GND_9") (pintype "power_in"))
      (node (ref "SJ1") (pin "P$1") (pinfunction "1_P$1") (pintype "passive"))
      (node (ref "SJ2") (pin "P$1") (pinfunction "1_P$1") (pintype "passive"))
      (node (ref "SJ3") (pin "1") (pinfunction "1_1") (pintype "passive"))
    )
    (net (code "42") (name "Net-(IC2-I1)") (class "Default")
      (node (ref "IC2") (pin "1") (pinfunction "I1_1") (pintype "input"))
      (node (ref "IC5") (pin "15") (pinfunction "QA_15") (pintype "tri_state"))
      (node (ref "R3") (pin "1") (pinfunction "1_1") (pintype "passive"))
    )
    (net (code "43") (name "Net-(IC2-I2)") (class "Default")
      (node (ref "IC2") (pin "2") (pinfunction "I2_2") (pintype "input"))
      (node (ref "IC5") (pin "1") (pinfunction "QB_1") (pintype "tri_state"))
      (node (ref "R4") (pin "1") (pinfunction "1_1") (pintype "passive"))
    )
    (net (code "44") (name "Net-(IC2-I3)") (class "Default")
      (node (ref "IC2") (pin "3") (pinfunction "I3_3") (pintype "input"))
      (node (ref "IC5") (pin "2") (pinfunction "QC_2") (pintype "tri_state"))
      (node (ref "R5") (pin "1") (pinfunction "1_1") (pintype "passive"))
    )
    (net (code "45") (name "Net-(IC2-I4)") (class "Default")
      (node (ref "IC2") (pin "4") (pinfunction "I4_4") (pintype "input"))
      (node (ref "IC5") (pin "3") (pinfunction "QD_3") (pintype "tri_state"))
      (node (ref "R6") (pin "1") (pinfunction "1_1") (pintype "passive"))
    )
    (net (code "46") (name "Net-(IC2-I5)") (class "Default")
      (node (ref "IC2") (pin "5") (pinfunction "I5_5") (pintype "input"))
      (node (ref "IC5") (pin "4") (pinfunction "QE_4") (pintype "tri_state"))
      (node (ref "R7") (pin "1") (pinfunction "1_1") (pintype "passive"))
    )
    (net (code "47") (name "Net-(IC2-I6)") (class "Default")
      (node (ref "IC2") (pin "6") (pinfunction "I6_6") (pintype "input"))
      (node (ref "IC5") (pin "5") (pinfunction "QF_5") (pintype "tri_state"))
      (node (ref "R8") (pin "1") (pinfunction "1_1") (pintype "passive"))
    )
    (net (code "48") (name "Net-(IC2-I7)") (class "Default")
      (node (ref "IC2") (pin "7") (pinfunction "I7_7") (pintype "input"))
      (node (ref "IC5") (pin "6") (pinfunction "QG_6") (pintype "tri_state"))
      (node (ref "R9") (pin "1") (pinfunction "1_1") (pintype "passive"))
    )
    (net (code "49") (name "Net-(IC2-I8)") (class "Default")
      (node (ref "IC2") (pin "8") (pinfunction "I8_8") (pintype "input"))
      (node (ref "IC5") (pin "7") (pinfunction "QH_7") (pintype "tri_state"))
      (node (ref "R10") (pin "1") (pinfunction "1_1") (pintype "passive"))
    )
    (net (code "50") (name "Net-(IC2-O1)") (class "Default")
      (node (ref "IC2") (pin "18") (pinfunction "O1_18") (pintype "open_collector"))
      (node (ref "JP1") (pin "1") (pinfunction "1_1") (pintype "passive"))
      (node (ref "Q1") (pin "3") (pinfunction "D_3") (pintype "passive"))
    )
    (net (code "51") (name "Net-(IC2-O2)") (class "Default")
      (node (ref "IC2") (pin "17") (pinfunction "O2_17") (pintype "open_collector"))
      (node (ref "JP1") (pin "2") (pinfunction "2_2") (pintype "passive"))
      (node (ref "Q2") (pin "3") (pinfunction "D_3") (pintype "passive"))
    )
    (net (code "52") (name "Net-(IC2-O3)") (class "Default")
      (node (ref "IC2") (pin "16") (pinfunction "O3_16") (pintype "open_collector"))
      (node (ref "JP1") (pin "3") (pinfunction "3_3") (pintype "passive"))
      (node (ref "Q3") (pin "3") (pinfunction "D_3") (pintype "passive"))
    )
    (net (code "53") (name "Net-(IC2-O4)") (class "Default")
      (node (ref "IC2") (pin "15") (pinfunction "O4_15") (pintype "open_collector"))
      (node (ref "JP1") (pin "4") (pinfunction "4_4") (pintype "passive"))
      (node (ref "Q4") (pin "3") (pinfunction "D_3") (pintype "passive"))
    )
    (net (code "54") (name "Net-(IC2-O5)") (class "Default")
      (node (ref "IC2") (pin "14") (pinfunction "O5_14") (pintype "open_collector"))
      (node (ref "JP1") (pin "5") (pinfunction "5_5") (pintype "passive"))
      (node (ref "Q5") (pin "3") (pinfunction "D_3") (pintype "passive"))
    )
    (net (code "55") (name "Net-(IC2-O6)") (class "Default")
      (node (ref "IC2") (pin "13") (pinfunction "O6_13") (pintype "open_collector"))
      (node (ref "JP1") (pin "6") (pinfunction "6_6") (pintype "passive"))
      (node (ref "Q6") (pin "3") (pinfunction "D_3") (pintype "passive"))
    )
    (net (code "56") (name "Net-(IC2-O7)") (class "Default")
      (node (ref "IC2") (pin "12") (pinfunction "O7_12") (pintype "open_collector"))
      (node (ref "JP1") (pin "7") (pinfunction "7_7") (pintype "passive"))
      (node (ref "Q7") (pin "3") (pinfunction "D_3") (pintype "passive"))
    )
    (net (code "57") (name "Net-(IC2-O8)") (class "Default")
      (node (ref "IC2") (pin "11") (pinfunction "O8_11") (pintype "open_collector"))
      (node (ref "JP1") (pin "8") (pinfunction "8_8") (pintype "passive"))
      (node (ref "Q8") (pin "3") (pinfunction "D_3") (pintype "passive"))
    )
    (net (code "58") (name "Net-(IC3A-QA)") (class "Default")
      (node (ref "IC3") (pin "15") (pinfunction "QA_15") (pintype "tri_state"))
      (node (ref "IC8") (pin "1") (pinfunction "I1_1") (pintype "input"))
      (node (ref "R11") (pin "1") (pinfunction "1_1") (pintype "passive"))
    )
    (net (code "59") (name "Net-(IC3A-QB)") (class "Default")
      (node (ref "IC3") (pin "1") (pinfunction "QB_1") (pintype "tri_state"))
      (node (ref "IC8") (pin "2") (pinfunction "I2_2") (pintype "input"))
      (node (ref "R12") (pin "1") (pinfunction "1_1") (pintype "passive"))
    )
    (net (code "60") (name "Net-(IC3A-QC)") (class "Default")
      (node (ref "IC3") (pin "2") (pinfunction "QC_2") (pintype "tri_state"))
      (node (ref "IC8") (pin "3") (pinfunction "I3_3") (pintype "input"))
      (node (ref "R13") (pin "1") (pinfunction "1_1") (pintype "passive"))
    )
    (net (code "61") (name "Net-(IC3A-QD)") (class "Default")
      (node (ref "IC3") (pin "3") (pinfunction "QD_3") (pintype "tri_state"))
      (node (ref "IC8") (pin "4") (pinfunction "I4_4") (pintype "input"))
      (node (ref "R14") (pin "1") (pinfunction "1_1") (pintype "passive"))
    )
    (net (code "62") (name "Net-(IC3A-QE)") (class "Default")
      (node (ref "IC3") (pin "4") (pinfunction "QE_4") (pintype "tri_state"))
      (node (ref "IC8") (pin "5") (pinfunction "I5_5") (pintype "input"))
      (node (ref "R15") (pin "1") (pinfunction "1_1") (pintype "passive"))
    )
    (net (code "63") (name "Net-(IC3A-QF)") (class "Default")
      (node (ref "IC3") (pin "5") (pinfunction "QF_5") (pintype "tri_state"))
      (node (ref "IC8") (pin "6") (pinfunction "I6_6") (pintype "input"))
      (node (ref "R16") (pin "1") (pinfunction "1_1") (pintype "passive"))
    )
    (net (code "64") (name "Net-(IC3A-QG)") (class "Default")
      (node (ref "IC3") (pin "6") (pinfunction "QG_6") (pintype "tri_state"))
      (node (ref "IC8") (pin "7") (pinfunction "I7_7") (pintype "input"))
      (node (ref "R17") (pin "1") (pinfunction "1_1") (pintype "passive"))
    )
    (net (code "65") (name "Net-(IC3A-QH)") (class "Default")
      (node (ref "IC3") (pin "7") (pinfunction "QH_7") (pintype "tri_state"))
      (node (ref "IC8") (pin "8") (pinfunction "I8_8") (pintype "input"))
      (node (ref "R18") (pin "1") (pinfunction "1_1") (pintype "passive"))
    )
    (net (code "66") (name "Net-(IC4A-A)") (class "Default")
      (node (ref "IC4") (pin "2") (pinfunction "A_2") (pintype "input"))
      (node (ref "R28") (pin "1") (pinfunction "1_1") (pintype "passive"))
      (node (ref "RN1") (pin "9") (pinfunction "2_9") (pintype "passive"))
    )
    (net (code "67") (name "Net-(IC4A-B)") (class "Default")
      (node (ref "IC4") (pin "3") (pinfunction "B_3") (pintype "input"))
      (node (ref "R29") (pin "1") (pinfunction "1_1") (pintype "passive"))
      (node (ref "RN1") (pin "10") (pinfunction "2_10") (pintype "passive"))
    )
    (net (code "68") (name "Net-(IC4A-C)") (class "Default")
      (node (ref "IC4") (pin "4") (pinfunction "C_4") (pintype "input"))
      (node (ref "R30") (pin "1") (pinfunction "1_1") (pintype "passive"))
      (node (ref "RN1") (pin "11") (pinfunction "2_11") (pintype "passive"))
    )
    (net (code "69") (name "Net-(IC4A-D)") (class "Default")
      (node (ref "IC4") (pin "5") (pinfunction "D_5") (pintype "input"))
      (node (ref "R31") (pin "1") (pinfunction "1_1") (pintype "passive"))
      (node (ref "RN1") (pin "12") (pinfunction "2_12") (pintype "passive"))
    )
    (net (code "70") (name "Net-(IC4A-E)") (class "Default")
      (node (ref "IC4") (pin "10") (pinfunction "E_10") (pintype "input"))
      (node (ref "R32") (pin "1") (pinfunction "1_1") (pintype "passive"))
      (node (ref "RN1") (pin "13") (pinfunction "2_13") (pintype "passive"))
    )
    (net (code "71") (name "Net-(IC4A-F)") (class "Default")
      (node (ref "IC4") (pin "11") (pinfunction "F_11") (pintype "input"))
      (node (ref "R33") (pin "1") (pinfunction "1_1") (pintype "passive"))
      (node (ref "RN1") (pin "14") (pinfunction "2_14") (pintype "passive"))
    )
    (net (code "72") (name "Net-(IC4A-G)") (class "Default")
      (node (ref "IC4") (pin "12") (pinfunction "G_12") (pintype "input"))
      (node (ref "R34") (pin "1") (pinfunction "1_1") (pintype "passive"))
      (node (ref "RN1") (pin "15") (pinfunction "2_15") (pintype "passive"))
    )
    (net (code "73") (name "Net-(IC4A-H)") (class "Default")
      (node (ref "IC4") (pin "14") (pinfunction "H_14") (pintype "input"))
      (node (ref "R35") (pin "1") (pinfunction "1_1") (pintype "passive"))
      (node (ref "RN1") (pin "16") (pinfunction "2_16") (pintype "passive"))
    )
    (net (code "74") (name "Net-(IC6A--IN)") (class "Default")
      (node (ref "IC6") (pin "13") (pinfunction "-IN_13") (pintype "input"))
      (node (ref "IC6") (pin "2") (pinfunction "-IN_2") (pintype "input"))
      (node (ref "IC6") (pin "6") (pinfunction "-IN_6") (pintype "input"))
      (node (ref "IC6") (pin "9") (pinfunction "-IN_9") (pintype "input"))
      (node (ref "IC9") (pin "13") (pinfunction "-IN_13") (pintype "input"))
      (node (ref "IC9") (pin "2") (pinfunction "-IN_2") (pintype "input"))
      (node (ref "IC9") (pin "6") (pinfunction "-IN_6") (pintype "input"))
      (node (ref "IC9") (pin "9") (pinfunction "-IN_9") (pintype "input"))
      (node (ref "R1") (pin "1") (pinfunction "1_1") (pintype "passive"))
      (node (ref "R2") (pin "2") (pinfunction "2_2") (pintype "passive"))
    )
    (net (code "75") (name "Net-(IC6A-OUT)") (class "Default")
      (node (ref "IC6") (pin "1") (pinfunction "OUT_1") (pintype "output"))
      (node (ref "JP15") (pin "3") (pinfunction "3_3") (pintype "passive"))
      (node (ref "JP5") (pin "3") (pinfunction "3_3") (pintype "passive"))
      (node (ref "U$5") (pin "5") (pinfunction "O_5") (pintype "output"))
    )
    (net (code "76") (name "Net-(IC6B-OUT)") (class "Default")
      (node (ref "IC6") (pin "7") (pinfunction "OUT_7") (pintype "output"))
      (node (ref "JP15") (pin "1") (pinfunction "1_1") (pintype "passive"))
      (node (ref "JP5") (pin "1") (pinfunction "1_1") (pintype "passive"))
      (node (ref "U$4") (pin "7") (pinfunction "O_7") (pintype "output"))
    )
    (net (code "77") (name "Net-(IC6C-OUT)") (class "Default")
      (node (ref "IC6") (pin "8") (pinfunction "OUT_8") (pintype "output"))
      (node (ref "JP15") (pin "2") (pinfunction "2_2") (pintype "passive"))
      (node (ref "JP5") (pin "2") (pinfunction "2_2") (pintype "passive"))
      (node (ref "U$4") (pin "5") (pinfunction "O_5") (pintype "output"))
    )
    (net (code "78") (name "Net-(IC6D-OUT)") (class "Default")
      (node (ref "IC6") (pin "14") (pinfunction "OUT_14") (pintype "output"))
      (node (ref "JP15") (pin "4") (pinfunction "4_4") (pintype "passive"))
      (node (ref "JP5") (pin "4") (pinfunction "4_4") (pintype "passive"))
      (node (ref "U$5") (pin "7") (pinfunction "O_7") (pintype "output"))
    )
    (net (code "79") (name "Net-(IC7-RS)") (class "Default")
      (node (ref "IC7") (pin "8") (pinfunction "RS_8") (pintype "input"))
      (node (ref "R61") (pin "1") (pinfunction "1_1") (pintype "passive"))
      (node (ref "U$6") (pin "8") (pinfunction "RS_8") (pintype "bidirectional"))
    )
    (net (code "80") (name "Net-(IC7-VREF)") (class "Default")
      (node (ref "IC7") (pin "5") (pinfunction "VREF_5") (pintype "output"))
      (node (ref "SJ18") (pin "P$2") (pinfunction "2_P$2") (pintype "passive"))
      (node (ref "U$6") (pin "5") (pinfunction "VREF_5") (pintype "bidirectional"))
    )
    (net (code "81") (name "Net-(IC8-CD+)") (class "Default")
      (node (ref "IC8") (pin "10") (pinfunction "CD+_10") (pintype "passive"))
      (node (ref "SJ10") (pin "P$1") (pinfunction "1_P$1") (pintype "passive"))
      (node (ref "SJ11") (pin "P$1") (pinfunction "1_P$1") (pintype "passive"))
      (node (ref "SJ12") (pin "P$1") (pinfunction "1_P$1") (pintype "passive"))
    )
    (net (code "82") (name "Net-(IC8-GND)") (class "Default")
      (node (ref "IC8") (pin "9") (pinfunction "GND_9") (pintype "power_in"))
      (node (ref "SJ7") (pin "P$1") (pinfunction "1_P$1") (pintype "passive"))
      (node (ref "SJ8") (pin "P$1") (pinfunction "1_P$1") (pintype "passive"))
      (node (ref "SJ9") (pin "1") (pinfunction "1_1") (pintype "passive"))
    )
    (net (code "83") (name "Net-(IC8-O1)") (class "Default")
      (node (ref "IC8") (pin "18") (pinfunction "O1_18") (pintype "open_collector"))
      (node (ref "JP6") (pin "1") (pinfunction "1_1") (pintype "passive"))
      (node (ref "Q9") (pin "3") (pinfunction "D_3") (pintype "passive"))
    )
    (net (code "84") (name "Net-(IC8-O2)") (class "Default")
      (node (ref "IC8") (pin "17") (pinfunction "O2_17") (pintype "open_collector"))
      (node (ref "JP6") (pin "2") (pinfunction "2_2") (pintype "passive"))
      (node (ref "Q10") (pin "3") (pinfunction "D_3") (pintype "passive"))
    )
    (net (code "85") (name "Net-(IC8-O3)") (class "Default")
      (node (ref "IC8") (pin "16") (pinfunction "O3_16") (pintype "open_collector"))
      (node (ref "JP6") (pin "3") (pinfunction "3_3") (pintype "passive"))
      (node (ref "Q11") (pin "3") (pinfunction "D_3") (pintype "passive"))
    )
    (net (code "86") (name "Net-(IC8-O4)") (class "Default")
      (node (ref "IC8") (pin "15") (pinfunction "O4_15") (pintype "open_collector"))
      (node (ref "JP6") (pin "4") (pinfunction "4_4") (pintype "passive"))
      (node (ref "Q12") (pin "3") (pinfunction "D_3") (pintype "passive"))
    )
    (net (code "87") (name "Net-(IC8-O5)") (class "Default")
      (node (ref "IC8") (pin "14") (pinfunction "O5_14") (pintype "open_collector"))
      (node (ref "JP6") (pin "5") (pinfunction "5_5") (pintype "passive"))
      (node (ref "Q13") (pin "3") (pinfunction "D_3") (pintype "passive"))
    )
    (net (code "88") (name "Net-(IC8-O6)") (class "Default")
      (node (ref "IC8") (pin "13") (pinfunction "O6_13") (pintype "open_collector"))
      (node (ref "JP6") (pin "6") (pinfunction "6_6") (pintype "passive"))
      (node (ref "Q14") (pin "3") (pinfunction "D_3") (pintype "passive"))
    )
    (net (code "89") (name "Net-(IC8-O7)") (class "Default")
      (node (ref "IC8") (pin "12") (pinfunction "O7_12") (pintype "open_collector"))
      (node (ref "JP6") (pin "7") (pinfunction "7_7") (pintype "passive"))
      (node (ref "Q15") (pin "3") (pinfunction "D_3") (pintype "passive"))
    )
    (net (code "90") (name "Net-(IC8-O8)") (class "Default")
      (node (ref "IC8") (pin "11") (pinfunction "O8_11") (pintype "open_collector"))
      (node (ref "JP6") (pin "8") (pinfunction "8_8") (pintype "passive"))
      (node (ref "Q16") (pin "3") (pinfunction "D_3") (pintype "passive"))
    )
    (net (code "91") (name "Net-(IC9A-OUT)") (class "Default")
      (node (ref "IC9") (pin "1") (pinfunction "OUT_1") (pintype "output"))
      (node (ref "JP15") (pin "9") (pinfunction "9_9") (pintype "passive"))
      (node (ref "JP5") (pin "7") (pinfunction "7_7") (pintype "passive"))
      (node (ref "U$3") (pin "5") (pinfunction "O_5") (pintype "output"))
    )
    (net (code "92") (name "Net-(IC9B-OUT)") (class "Default")
      (node (ref "IC9") (pin "7") (pinfunction "OUT_7") (pintype "output"))
      (node (ref "JP15") (pin "7") (pinfunction "7_7") (pintype "passive"))
      (node (ref "JP5") (pin "5") (pinfunction "5_5") (pintype "passive"))
      (node (ref "U$2") (pin "7") (pinfunction "O_7") (pintype "output"))
    )
    (net (code "93") (name "Net-(IC9C-OUT)") (class "Default")
      (node (ref "IC9") (pin "8") (pinfunction "OUT_8") (pintype "output"))
      (node (ref "JP15") (pin "8") (pinfunction "8_8") (pintype "passive"))
      (node (ref "JP5") (pin "6") (pinfunction "6_6") (pintype "passive"))
      (node (ref "U$2") (pin "5") (pinfunction "O_5") (pintype "output"))
    )
    (net (code "94") (name "Net-(IC9D-OUT)") (class "Default")
      (node (ref "IC9") (pin "14") (pinfunction "OUT_14") (pintype "output"))
      (node (ref "JP15") (pin "10") (pinfunction "10_10") (pintype "passive"))
      (node (ref "JP5") (pin "8") (pinfunction "8_8") (pintype "passive"))
      (node (ref "U$3") (pin "7") (pinfunction "O_7") (pintype "output"))
    )
    (net (code "95") (name "Net-(J1-Pad4)") (class "Default")
      (node (ref "J1") (pin "4") (pinfunction "4_4") (pintype "passive"))
      (node (ref "J2") (pin "4") (pinfunction "4_4") (pintype "passive"))
    )
    (net (code "96") (name "Net-(J1-Pad5)") (class "Default")
      (node (ref "J1") (pin "5") (pinfunction "5_5") (pintype "passive"))
      (node (ref "J2") (pin "5") (pinfunction "5_5") (pintype "passive"))
    )
    (net (code "97") (name "Net-(J1-Pad8)") (class "Default")
      (node (ref "J1") (pin "8") (pinfunction "8_8") (pintype "passive"))
      (node (ref "J2") (pin "8") (pinfunction "8_8") (pintype "passive"))
      (node (ref "R40") (pin "1") (pinfunction "1_1") (pintype "passive"))
    )
    (net (code "98") (name "Net-(JP4-Pad3)") (class "Default")
      (node (ref "JP4") (pin "3") (pinfunction "3_3") (pintype "passive"))
      (node (ref "R40") (pin "2") (pinfunction "2_2") (pintype "passive"))
    )
    (net (code "99") (name "Net-(JP13-Pad1)") (class "Default")
      (node (ref "JP13") (pin "1") (pinfunction "1_1") (pintype "passive"))
      (node (ref "JP3") (pin "1") (pinfunction "1_1") (pintype "passive"))
      (node (ref "R44") (pin "2") (pinfunction "2_2") (pintype "passive"))
      (node (ref "R53") (pin "2") (pinfunction "2_2") (pintype "passive"))
      (node (ref "RN4") (pin "1") (pinfunction "1_1") (pintype "passive"))
      (node (ref "RN5") (pin "9") (pinfunction "9_9") (pintype "passive"))
    )
    (net (code "100") (name "Net-(JP14-Pad1)") (class "Default")
      (node (ref "JP14") (pin "1") (pinfunction "1_1") (pintype "passive"))
      (node (ref "JP2") (pin "1") (pinfunction "1_1") (pintype "passive"))
      (node (ref "R35") (pin "2") (pinfunction "2_2") (pintype "passive"))
      (node (ref "R45") (pin "2") (pinfunction "2_2") (pintype "passive"))
      (node (ref "RN1") (pin "1") (pinfunction "1_1") (pintype "passive"))
      (node (ref "RN2") (pin "9") (pinfunction "9_9") (pintype "passive"))
    )
    (net (code "101") (name "Net-(Q1-G)") (class "Default")
      (node (ref "Q1") (pin "1") (pinfunction "G_1") (pintype "passive"))
      (node (ref "R3") (pin "2") (pinfunction "2_2") (pintype "passive"))
    )
    (net (code "102") (name "Net-(Q2-G)") (class "Default")
      (node (ref "Q2") (pin "1") (pinfunction "G_1") (pintype "passive"))
      (node (ref "R4") (pin "2") (pinfunction "2_2") (pintype "passive"))
    )
    (net (code "103") (name "Net-(Q3-G)") (class "Default")
      (node (ref "Q3") (pin "1") (pinfunction "G_1") (pintype "passive"))
      (node (ref "R5") (pin "2") (pinfunction "2_2") (pintype "passive"))
    )
    (net (code "104") (name "Net-(Q4-G)") (class "Default")
      (node (ref "Q4") (pin "1") (pinfunction "G_1") (pintype "passive"))
      (node (ref "R6") (pin "2") (pinfunction "2_2") (pintype "passive"))
    )
    (net (code "105") (name "Net-(Q5-G)") (class "Default")
      (node (ref "Q5") (pin "1") (pinfunction "G_1") (pintype "passive"))
      (node (ref "R7") (pin "2") (pinfunction "2_2") (pintype "passive"))
    )
    (net (code "106") (name "Net-(Q6-G)") (class "Default")
      (node (ref "Q6") (pin "1") (pinfunction "G_1") (pintype "passive"))
      (node (ref "R8") (pin "2") (pinfunction "2_2") (pintype "passive"))
    )
    (net (code "107") (name "Net-(Q7-G)") (class "Default")
      (node (ref "Q7") (pin "1") (pinfunction "G_1") (pintype "passive"))
      (node (ref "R9") (pin "2") (pinfunction "2_2") (pintype "passive"))
    )
    (net (code "108") (name "Net-(Q8-G)") (class "Default")
      (node (ref "Q8") (pin "1") (pinfunction "G_1") (pintype "passive"))
      (node (ref "R10") (pin "2") (pinfunction "2_2") (pintype "passive"))
    )
    (net (code "109") (name "Net-(Q9-G)") (class "Default")
      (node (ref "Q9") (pin "1") (pinfunction "G_1") (pintype "passive"))
      (node (ref "R11") (pin "2") (pinfunction "2_2") (pintype "passive"))
    )
    (net (code "110") (name "Net-(Q10-G)") (class "Default")
      (node (ref "Q10") (pin "1") (pinfunction "G_1") (pintype "passive"))
      (node (ref "R12") (pin "2") (pinfunction "2_2") (pintype "passive"))
    )
    (net (code "111") (name "Net-(Q11-G)") (class "Default")
      (node (ref "Q11") (pin "1") (pinfunction "G_1") (pintype "passive"))
      (node (ref "R13") (pin "2") (pinfunction "2_2") (pintype "passive"))
    )
    (net (code "112") (name "Net-(Q12-G)") (class "Default")
      (node (ref "Q12") (pin "1") (pinfunction "G_1") (pintype "passive"))
      (node (ref "R14") (pin "2") (pinfunction "2_2") (pintype "passive"))
    )
    (net (code "113") (name "Net-(Q13-G)") (class "Default")
      (node (ref "Q13") (pin "1") (pinfunction "G_1") (pintype "passive"))
      (node (ref "R15") (pin "2") (pinfunction "2_2") (pintype "passive"))
    )
    (net (code "114") (name "Net-(Q14-G)") (class "Default")
      (node (ref "Q14") (pin "1") (pinfunction "G_1") (pintype "passive"))
      (node (ref "R16") (pin "2") (pinfunction "2_2") (pintype "passive"))
    )
    (net (code "115") (name "Net-(Q15-G)") (class "Default")
      (node (ref "Q15") (pin "1") (pinfunction "G_1") (pintype "passive"))
      (node (ref "R17") (pin "2") (pinfunction "2_2") (pintype "passive"))
    )
    (net (code "116") (name "Net-(Q16-G)") (class "Default")
      (node (ref "Q16") (pin "1") (pinfunction "G_1") (pintype "passive"))
      (node (ref "R18") (pin "2") (pinfunction "2_2") (pintype "passive"))
    )
    (net (code "117") (name "Net-(RN1B-1)") (class "Default")
      (node (ref "JP14") (pin "2") (pinfunction "2_2") (pintype "passive"))
      (node (ref "JP2") (pin "2") (pinfunction "2_2") (pintype "passive"))
      (node (ref "R34") (pin "2") (pinfunction "2_2") (pintype "passive"))
      (node (ref "R46") (pin "1") (pinfunction "1_1") (pintype "passive"))
      (node (ref "RN1") (pin "2") (pinfunction "1_2") (pintype "passive"))
      (node (ref "RN2") (pin "8") (pinfunction "8_8") (pintype "passive"))
    )
    (net (code "118") (name "Net-(RN1C-1)") (class "Default")
      (node (ref "JP14") (pin "3") (pinfunction "3_3") (pintype "passive"))
      (node (ref "JP2") (pin "3") (pinfunction "3_3") (pintype "passive"))
      (node (ref "R33") (pin "2") (pinfunction "2_2") (pintype "passive"))
      (node (ref "R47") (pin "1") (pinfunction "1_1") (pintype "passive"))
      (node (ref "RN1") (pin "3") (pinfunction "1_3") (pintype "passive"))
      (node (ref "RN2") (pin "7") (pinfunction "7_7") (pintype "passive"))
    )
    (net (code "119") (name "Net-(RN1D-1)") (class "Default")
      (node (ref "JP14") (pin "4") (pinfunction "4_4") (pintype "passive"))
      (node (ref "JP2") (pin "4") (pinfunction "4_4") (pintype "passive"))
      (node (ref "R32") (pin "2") (pinfunction "2_2") (pintype "passive"))
      (node (ref "R48") (pin "1") (pinfunction "1_1") (pintype "passive"))
      (node (ref "RN1") (pin "4") (pinfunction "1_4") (pintype "passive"))
      (node (ref "RN2") (pin "6") (pinfunction "6_6") (pintype "passive"))
    )
    (net (code "120") (name "Net-(RN1E-1)") (class "Default")
      (node (ref "JP14") (pin "7") (pinfunction "7_7") (pintype "passive"))
      (node (ref "JP2") (pin "5") (pinfunction "5_5") (pintype "passive"))
      (node (ref "R31") (pin "2") (pinfunction "2_2") (pintype "passive"))
      (node (ref "R49") (pin "1") (pinfunction "1_1") (pintype "passive"))
      (node (ref "RN1") (pin "5") (pinfunction "1_5") (pintype "passive"))
      (node (ref "RN2") (pin "5") (pinfunction "5_5") (pintype "passive"))
    )
    (net (code "121") (name "Net-(RN1F-1)") (class "Default")
      (node (ref "JP14") (pin "8") (pinfunction "8_8") (pintype "passive"))
      (node (ref "JP2") (pin "6") (pinfunction "6_6") (pintype "passive"))
      (node (ref "R30") (pin "2") (pinfunction "2_2") (pintype "passive"))
      (node (ref "R50") (pin "1") (pinfunction "1_1") (pintype "passive"))
      (node (ref "RN1") (pin "6") (pinfunction "1_6") (pintype "passive"))
      (node (ref "RN2") (pin "4") (pinfunction "4_4") (pintype "passive"))
    )
    (net (code "122") (name "Net-(RN1G-1)") (class "Default")
      (node (ref "JP14") (pin "9") (pinfunction "9_9") (pintype "passive"))
      (node (ref "JP2") (pin "7") (pinfunction "7_7") (pintype "passive"))
      (node (ref "R29") (pin "2") (pinfunction "2_2") (pintype "passive"))
      (node (ref "R51") (pin "1") (pinfunction "1_1") (pintype "passive"))
      (node (ref "RN1") (pin "7") (pinfunction "1_7") (pintype "passive"))
      (node (ref "RN2") (pin "3") (pinfunction "3_3") (pintype "passive"))
    )
    (net (code "123") (name "Net-(RN1H-1)") (class "Default")
      (node (ref "JP14") (pin "10") (pinfunction "10_10") (pintype "passive"))
      (node (ref "JP2") (pin "8") (pinfunction "8_8") (pintype "passive"))
      (node (ref "R28") (pin "2") (pinfunction "2_2") (pintype "passive"))
      (node (ref "R52") (pin "1") (pinfunction "1_1") (pintype "passive"))
      (node (ref "RN1") (pin "8") (pinfunction "1_8") (pintype "passive"))
      (node (ref "RN2") (pin "2") (pinfunction "2_2") (pintype "passive"))
    )
    (net (code "124") (name "Net-(RN4B-1)") (class "Default")
      (node (ref "JP13") (pin "2") (pinfunction "2_2") (pintype "passive"))
      (node (ref "JP3") (pin "2") (pinfunction "2_2") (pintype "passive"))
      (node (ref "R43") (pin "2") (pinfunction "2_2") (pintype "passive"))
      (node (ref "R54") (pin "2") (pinfunction "2_2") (pintype "passive"))
      (node (ref "RN4") (pin "2") (pinfunction "1_2") (pintype "passive"))
      (node (ref "RN5") (pin "8") (pinfunction "8_8") (pintype "passive"))
    )
    (net (code "125") (name "Net-(RN4C-1)") (class "Default")
      (node (ref "JP13") (pin "3") (pinfunction "3_3") (pintype "passive"))
      (node (ref "JP3") (pin "3") (pinfunction "3_3") (pintype "passive"))
      (node (ref "R42") (pin "2") (pinfunction "2_2") (pintype "passive"))
      (node (ref "R55") (pin "2") (pinfunction "2_2") (pintype "passive"))
      (node (ref "RN4") (pin "3") (pinfunction "1_3") (pintype "passive"))
      (node (ref "RN5") (pin "7") (pinfunction "7_7") (pintype "passive"))
    )
    (net (code "126") (name "Net-(RN4D-1)") (class "Default")
      (node (ref "JP13") (pin "4") (pinfunction "4_4") (pintype "passive"))
      (node (ref "JP3") (pin "4") (pinfunction "4_4") (pintype "passive"))
      (node (ref "R41") (pin "2") (pinfunction "2_2") (pintype "passive"))
      (node (ref "R56") (pin "2") (pinfunction "2_2") (pintype "passive"))
      (node (ref "RN4") (pin "4") (pinfunction "1_4") (pintype "passive"))
      (node (ref "RN5") (pin "6") (pinfunction "6_6") (pintype "passive"))
    )
    (net (code "127") (name "Net-(RN4E-1)") (class "Default")
      (node (ref "JP13") (pin "7") (pinfunction "7_7") (pintype "passive"))
      (node (ref "JP3") (pin "5") (pinfunction "5_5") (pintype "passive"))
      (node (ref "R39") (pin "2") (pinfunction "2_2") (pintype "passive"))
      (node (ref "R57") (pin "2") (pinfunction "2_2") (pintype "passive"))
      (node (ref "RN4") (pin "5") (pinfunction "1_5") (pintype "passive"))
      (node (ref "RN5") (pin "5") (pinfunction "5_5") (pintype "passive"))
    )
    (net (code "128") (name "Net-(RN4F-1)") (class "Default")
      (node (ref "JP13") (pin "8") (pinfunction "8_8") (pintype "passive"))
      (node (ref "JP3") (pin "6") (pinfunction "6_6") (pintype "passive"))
      (node (ref "R38") (pin "2") (pinfunction "2_2") (pintype "passive"))
      (node (ref "R58") (pin "2") (pinfunction "2_2") (pintype "passive"))
      (node (ref "RN4") (pin "6") (pinfunction "1_6") (pintype "passive"))
      (node (ref "RN5") (pin "4") (pinfunction "4_4") (pintype "passive"))
    )
    (net (code "129") (name "Net-(RN4G-1)") (class "Default")
      (node (ref "JP13") (pin "9") (pinfunction "9_9") (pintype "passive"))
      (node (ref "JP3") (pin "7") (pinfunction "7_7") (pintype "passive"))
      (node (ref "R37") (pin "2") (pinfunction "2_2") (pintype "passive"))
      (node (ref "R59") (pin "2") (pinfunction "2_2") (pintype "passive"))
      (node (ref "RN4") (pin "7") (pinfunction "1_7") (pintype "passive"))
      (node (ref "RN5") (pin "3") (pinfunction "3_3") (pintype "passive"))
    )
    (net (code "130") (name "Net-(RN4H-1)") (class "Default")
      (node (ref "JP13") (pin "10") (pinfunction "10_10") (pintype "passive"))
      (node (ref "JP3") (pin "8") (pinfunction "8_8") (pintype "passive"))
      (node (ref "R36") (pin "2") (pinfunction "2_2") (pintype "passive"))
      (node (ref "R60") (pin "2") (pinfunction "2_2") (pintype "passive"))
      (node (ref "RN4") (pin "8") (pinfunction "1_8") (pintype "passive"))
      (node (ref "RN5") (pin "2") (pinfunction "2_2") (pintype "passive"))
    )
    (net (code "131") (name "Net-(SJ13-1)") (class "Default")
      (node (ref "SJ13") (pin "P$1") (pinfunction "1_P$1") (pintype "passive"))
      (node (ref "U$1") (pin "PB14") (pinfunction "PB14_PB14") (pintype "bidirectional"))
    )
    (net (code "132") (name "Net-(SJ14-1)") (class "Default")
      (node (ref "SJ14") (pin "P$1") (pinfunction "1_P$1") (pintype "passive"))
      (node (ref "U$1") (pin "VIN2") (pinfunction "VIN2_VIN2") (pintype "power_in"))
    )
    (net (code "133") (name "Net-(SJ16-2)") (class "Default")
      (node (ref "JP9") (pin "2") (pinfunction "2_2") (pintype "passive"))
      (node (ref "SJ15") (pin "2") (pinfunction "2_2") (pintype "passive"))
      (node (ref "SJ16") (pin "P$2") (pinfunction "2_P$2") (pintype "passive"))
    )
    (net (code "134") (name "OLAT") (class "Default")
      (node (ref "IC3") (pin "12") (pinfunction "RCK_12") (pintype "input"))
      (node (ref "IC5") (pin "12") (pinfunction "RCK_12") (pintype "input"))
      (node (ref "R21") (pin "1") (pinfunction "1_1") (pintype "passive"))
      (node (ref "U$1") (pin "PA8") (pinfunction "PA8_PA8") (pintype "bidirectional"))
    )
    (net (code "135") (name "SCK") (class "Default")
      (node (ref "IC3") (pin "11") (pinfunction "SCK_11") (pintype "input"))
      (node (ref "IC5") (pin "11") (pinfunction "SCK_11") (pintype "input"))
      (node (ref "JP9") (pin "3") (pinfunction "3_3") (pintype "passive"))
      (node (ref "R19") (pin "1") (pinfunction "1_1") (pintype "passive"))
      (node (ref "U$1") (pin "PB3") (pinfunction "PB3_PB3") (pintype "bidirectional"))
    )
    (net (code "136") (name "SCK2") (class "Default")
      (node (ref "IC1") (pin "7") (pinfunction "CLK_7") (pintype "input"))
      (node (ref "IC4") (pin "7") (pinfunction "CLK_7") (pintype "input"))
      (node (ref "U$1") (pin "PB10") (pinfunction "PB10_PB10") (pintype "bidirectional"))
    )
    (net (code "137") (name "SLNK1") (class "Default")
      (node (ref "IC3") (pin "14") (pinfunction "SER_14") (pintype "input"))
      (node (ref "IC5") (pin "9") (pinfunction "QH*_9") (pintype "tri_state"))
      (node (ref "SJ17") (pin "P$1") (pinfunction "1_P$1") (pintype "passive"))
    )
    (net (code "138") (name "SLNK2") (class "Default")
      (node (ref "IC3") (pin "9") (pinfunction "QH*_9") (pintype "tri_state"))
      (node (ref "SJ16") (pin "P$1") (pinfunction "1_P$1") (pintype "passive"))
    )
    (net (code "139") (name "SLNK3") (class "Default")
      (node (ref "IC1") (pin "13") (pinfunction "QH_13") (pintype "output"))
      (node (ref "IC4") (pin "1") (pinfunction "SER_1") (pintype "input"))
    )
    (net (code "140") (name "SRV1") (class "Default")
      (node (ref "JP7") (pin "2") (pinfunction "2_2") (pintype "passive"))
      (node (ref "R25") (pin "2") (pinfunction "2_2") (pintype "passive"))
      (node (ref "U$1") (pin "PC9") (pinfunction "PC9_PC9") (pintype "bidirectional"))
    )
    (net (code "141") (name "SRV2") (class "Default")
      (node (ref "JP7") (pin "1") (pinfunction "1_1") (pintype "passive"))
      (node (ref "R24") (pin "2") (pinfunction "2_2") (pintype "passive"))
      (node (ref "U$1") (pin "PC7") (pinfunction "PC7_PC7") (pintype "bidirectional"))
    )
    (net (code "142") (name "SRV3") (class "Default")
      (node (ref "JP11") (pin "2") (pinfunction "2_2") (pintype "passive"))
      (node (ref "R26") (pin "2") (pinfunction "2_2") (pintype "passive"))
      (node (ref "U$1") (pin "PC8") (pinfunction "PC8_PC8") (pintype "bidirectional"))
    )
    (net (code "143") (name "SRV4") (class "Default")
      (node (ref "JP11") (pin "1") (pinfunction "1_1") (pintype "passive"))
      (node (ref "R27") (pin "2") (pinfunction "2_2") (pintype "passive"))
      (node (ref "U$1") (pin "PC6") (pinfunction "PC6_PC6") (pintype "bidirectional"))
    )
    (net (code "144") (name "SRV5") (class "Default")
      (node (ref "JP12") (pin "2") (pinfunction "2_2") (pintype "passive"))
      (node (ref "R64") (pin "2") (pinfunction "2_2") (pintype "passive"))
      (node (ref "U$1") (pin "PF1-PH1") (pinfunction "PF1-PH1_PF1-PH1") (pintype "bidirectional"))
    )
    (net (code "145") (name "SRV6") (class "Default")
      (node (ref "JP12") (pin "1") (pinfunction "1_1") (pintype "passive"))
      (node (ref "R65") (pin "2") (pinfunction "2_2") (pintype "passive"))
      (node (ref "U$1") (pin "PA15") (pinfunction "PA15_PA15") (pintype "bidirectional"))
    )
    (net (code "146") (name "SRV7") (class "Default")
      (node (ref "JP16") (pin "2") (pinfunction "2_2") (pintype "passive"))
      (node (ref "R66") (pin "2") (pinfunction "2_2") (pintype "passive"))
      (node (ref "U$1") (pin "PC12") (pinfunction "PC12_PC12") (pintype "bidirectional"))
    )
    (net (code "147") (name "SRV8") (class "Default")
      (node (ref "JP16") (pin "1") (pinfunction "1_1") (pintype "passive"))
      (node (ref "R67") (pin "2") (pinfunction "2_2") (pintype "passive"))
      (node (ref "U$1") (pin "PD2") (pinfunction "PD2_PD2") (pintype "bidirectional"))
    )
    (net (code "148") (name "TIN3") (class "Default")
      (node (ref "IC9") (pin "10") (pinfunction "+IN_10") (pintype "input"))
      (node (ref "U$1") (pin "PB15") (pinfunction "PB15_PB15") (pintype "bidirectional"))
      (node (ref "U$2") (pin "4") (pinfunction "I_4") (pintype "input"))
    )
    (net (code "149") (name "TIN4") (class "Default")
      (node (ref "IC9") (pin "12") (pinfunction "+IN_12") (pintype "input"))
      (node (ref "U$1") (pin "PB12") (pinfunction "PB12_PB12") (pintype "bidirectional"))
      (node (ref "U$3") (pin "2") (pinfunction "I_2") (pintype "input"))
    )
    (net (code "150") (name "V+") (class "Default")
      (node (ref "AP1509") (pin "3") (pinfunction "FB_3") (pintype "bidirectional"))
      (node (ref "C1") (pin "1") (pinfunction "1_1") (pintype "passive"))
      (node (ref "C2") (pin "+") (pinfunction "+_+") (pintype "passive"))
      (node (ref "IC10") (pin "1") (pinfunction "FB_1") (pintype "input"))
      (node (ref "L1") (pin "1") (pinfunction "1_1") (pintype "passive"))
      (node (ref "U$1") (pin "E5V") (pinfunction "E5V_E5V") (pintype "power_in"))
    )
    (net (code "151") (name "unconnected-(H1-MOUNT-PadB3,3)") (class "Default")
      (node (ref "H1") (pin "B3,3") (pinfunction "MOUNT_B3,3") (pintype "passive"))
    )
    (net (code "152") (name "unconnected-(H2-MOUNT-PadB3,3)") (class "Default")
      (node (ref "H2") (pin "B3,3") (pinfunction "MOUNT_B3,3") (pintype "passive"))
    )
    (net (code "153") (name "unconnected-(H3-MOUNT-PadB3,3)") (class "Default")
      (node (ref "H3") (pin "B3,3") (pinfunction "MOUNT_B3,3") (pintype "passive"))
    )
    (net (code "154") (name "unconnected-(H4-MOUNT-PadB3,3)") (class "Default")
      (node (ref "H4") (pin "B3,3") (pinfunction "MOUNT_B3,3") (pintype "passive"))
    )
    (net (code "155") (name "unconnected-(J3-Pad2)") (class "Default")
      (node (ref "J3") (pin "2") (pinfunction "2_2") (pintype "passive"))
    )
    (net (code "156") (name "unconnected-(U$1-PadBOOT0)") (class "Default")
      (node (ref "U$1") (pin "BOOT0") (pinfunction "BOOT0_BOOT0") (pintype "bidirectional"))
    )
    (net (code "157") (name "unconnected-(U$1-PadIOREF2)") (class "Default")
      (node (ref "U$1") (pin "IOREF2") (pinfunction "IOREF2_IOREF2") (pintype "input"))
    )
    (net (code "158") (name "unconnected-(U$1-PadNC1-PF7)") (class "Default")
      (node (ref "U$1") (pin "NC1-PF7") (pinfunction "NC1-PF7_NC1-PF7") (pintype "bidirectional"))
    )
    (net (code "159") (name "unconnected-(U$1-PadNC2-PF6)") (class "Default")
      (node (ref "U$1") (pin "NC2-PF6") (pinfunction "NC2-PF6_NC2-PF6") (pintype "bidirectional"))
    )
    (net (code "160") (name "unconnected-(U$1-PadNC3)") (class "Default")
      (node (ref "U$1") (pin "NC3") (pinfunction "NC3_NC3") (pintype "no_connect"))
    )
    (net (code "161") (name "unconnected-(U$1-PadNC4)") (class "Default")
      (node (ref "U$1") (pin "NC4") (pinfunction "NC4_NC4") (pintype "no_connect"))
    )
    (net (code "162") (name "unconnected-(U$1-PadNC5-PD8)") (class "Default")
      (node (ref "U$1") (pin "NC5-PD8") (pinfunction "NC5-PD8_NC5-PD8") (pintype "bidirectional"))
    )
    (net (code "163") (name "unconnected-(U$1-PadNC6-PB11)") (class "Default")
      (node (ref "U$1") (pin "NC6-PB11") (pinfunction "NC6-PB11_NC6-PB11") (pintype "no_connect"))
    )
    (net (code "164") (name "unconnected-(U$1-PadNC7-PF5)") (class "Default")
      (node (ref "U$1") (pin "NC7-PF5") (pinfunction "NC7-PF5_NC7-PF5") (pintype "bidirectional"))
    )
    (net (code "165") (name "unconnected-(U$1-PadNC8-PF4)") (class "Default")
      (node (ref "U$1") (pin "NC8-PF4") (pinfunction "NC8-PF4_NC8-PF4") (pintype "bidirectional"))
    )
    (net (code "166") (name "unconnected-(U$1-PadNRESET)") (class "Default")
      (node (ref "U$1") (pin "NRESET") (pinfunction "NRESET_NRESET") (pintype "input"))
    )
    (net (code "167") (name "unconnected-(U$1-PadPA1)") (class "Default")
      (node (ref "U$1") (pin "PA1") (pinfunction "PA1_PA1") (pintype "bidirectional"))
    )
    (net (code "168") (name "unconnected-(U$1-PadPA2)") (class "Default")
      (node (ref "U$1") (pin "PA2") (pinfunction "PA2_PA2") (pintype "bidirectional"))
    )
    (net (code "169") (name "unconnected-(U$1-PadPA3)") (class "Default")
      (node (ref "U$1") (pin "PA3") (pinfunction "PA3_PA3") (pintype "bidirectional"))
    )
    (net (code "170") (name "unconnected-(U$1-PadPA5)") (class "Default")
      (node (ref "U$1") (pin "PA5") (pinfunction "PA5_PA5") (pintype "bidirectional"))
    )
    (net (code "171") (name "unconnected-(U$1-PadPA7)") (class "Default")
      (node (ref "U$1") (pin "PA7") (pinfunction "PA7_PA7") (pintype "bidirectional"))
    )
    (net (code "172") (name "unconnected-(U$1-PadPA9)") (class "Default")
      (node (ref "U$1") (pin "PA9") (pinfunction "PA9_PA9") (pintype "bidirectional"))
    )
    (net (code "173") (name "unconnected-(U$1-PadPA10)") (class "Default")
      (node (ref "U$1") (pin "PA10") (pinfunction "PA10_PA10") (pintype "bidirectional"))
    )
    (net (code "174") (name "unconnected-(U$1-PadPA11)") (class "Default")
      (node (ref "U$1") (pin "PA11") (pinfunction "PA11_PA11") (pintype "bidirectional"))
    )
    (net (code "175") (name "unconnected-(U$1-PadPA12)") (class "Default")
      (node (ref "U$1") (pin "PA12") (pinfunction "PA12_PA12") (pintype "bidirectional"))
    )
    (net (code "176") (name "unconnected-(U$1-PadPA13)") (class "Default")
      (node (ref "U$1") (pin "PA13") (pinfunction "PA13_PA13") (pintype "bidirectional"))
    )
    (net (code "177") (name "unconnected-(U$1-PadPA14)") (class "Default")
      (node (ref "U$1") (pin "PA14") (pinfunction "PA14_PA14") (pintype "bidirectional"))
    )
    (net (code "178") (name "unconnected-(U$1-PadPB0)") (class "Default")
      (node (ref "U$1") (pin "PB0") (pinfunction "PB0_PB0") (pintype "bidirectional"))
    )
    (net (code "179") (name "unconnected-(U$1-PadPB13)") (class "Default")
      (node (ref "U$1") (pin "PB13") (pinfunction "PB13_PB13") (pintype "bidirectional"))
    )
    (net (code "180") (name "unconnected-(U$1-PadPC1)") (class "Default")
      (node (ref "U$1") (pin "PC1") (pinfunction "PC1_PC1") (pintype "bidirectional"))
    )
    (net (code "181") (name "unconnected-(U$1-PadPC4)") (class "Default")
      (node (ref "U$1") (pin "PC4") (pinfunction "PC4_PC4") (pintype "bidirectional"))
    )
    (net (code "182") (name "unconnected-(U$1-PadPC5)") (class "Default")
      (node (ref "U$1") (pin "PC5") (pinfunction "PC5_PC5") (pintype "bidirectional"))
    )
    (net (code "183") (name "unconnected-(U$1-PadPC13)") (class "Default")
      (node (ref "U$1") (pin "PC13") (pinfunction "PC13_PC13") (pintype "bidirectional"))
    )
    (net (code "184") (name "unconnected-(U$1-PadPC14)") (class "Default")
      (node (ref "U$1") (pin "PC14") (pinfunction "PC14_PC14") (pintype "bidirectional"))
    )
    (net (code "185") (name "unconnected-(U$1-PadPC15)") (class "Default")
      (node (ref "U$1") (pin "PC15") (pinfunction "PC15_PC15") (pintype "bidirectional"))
    )
    (net (code "186") (name "unconnected-(U$1-PadPF0-PH0)") (class "Default")
      (node (ref "U$1") (pin "PF0-PH0") (pinfunction "PF0-PH0_PF0-PH0") (pintype "bidirectional"))
    )
  )
)
